# XMICRO-SERIAL_V1_1.net
KiCad netlist of a schematic drawn in EAGLE
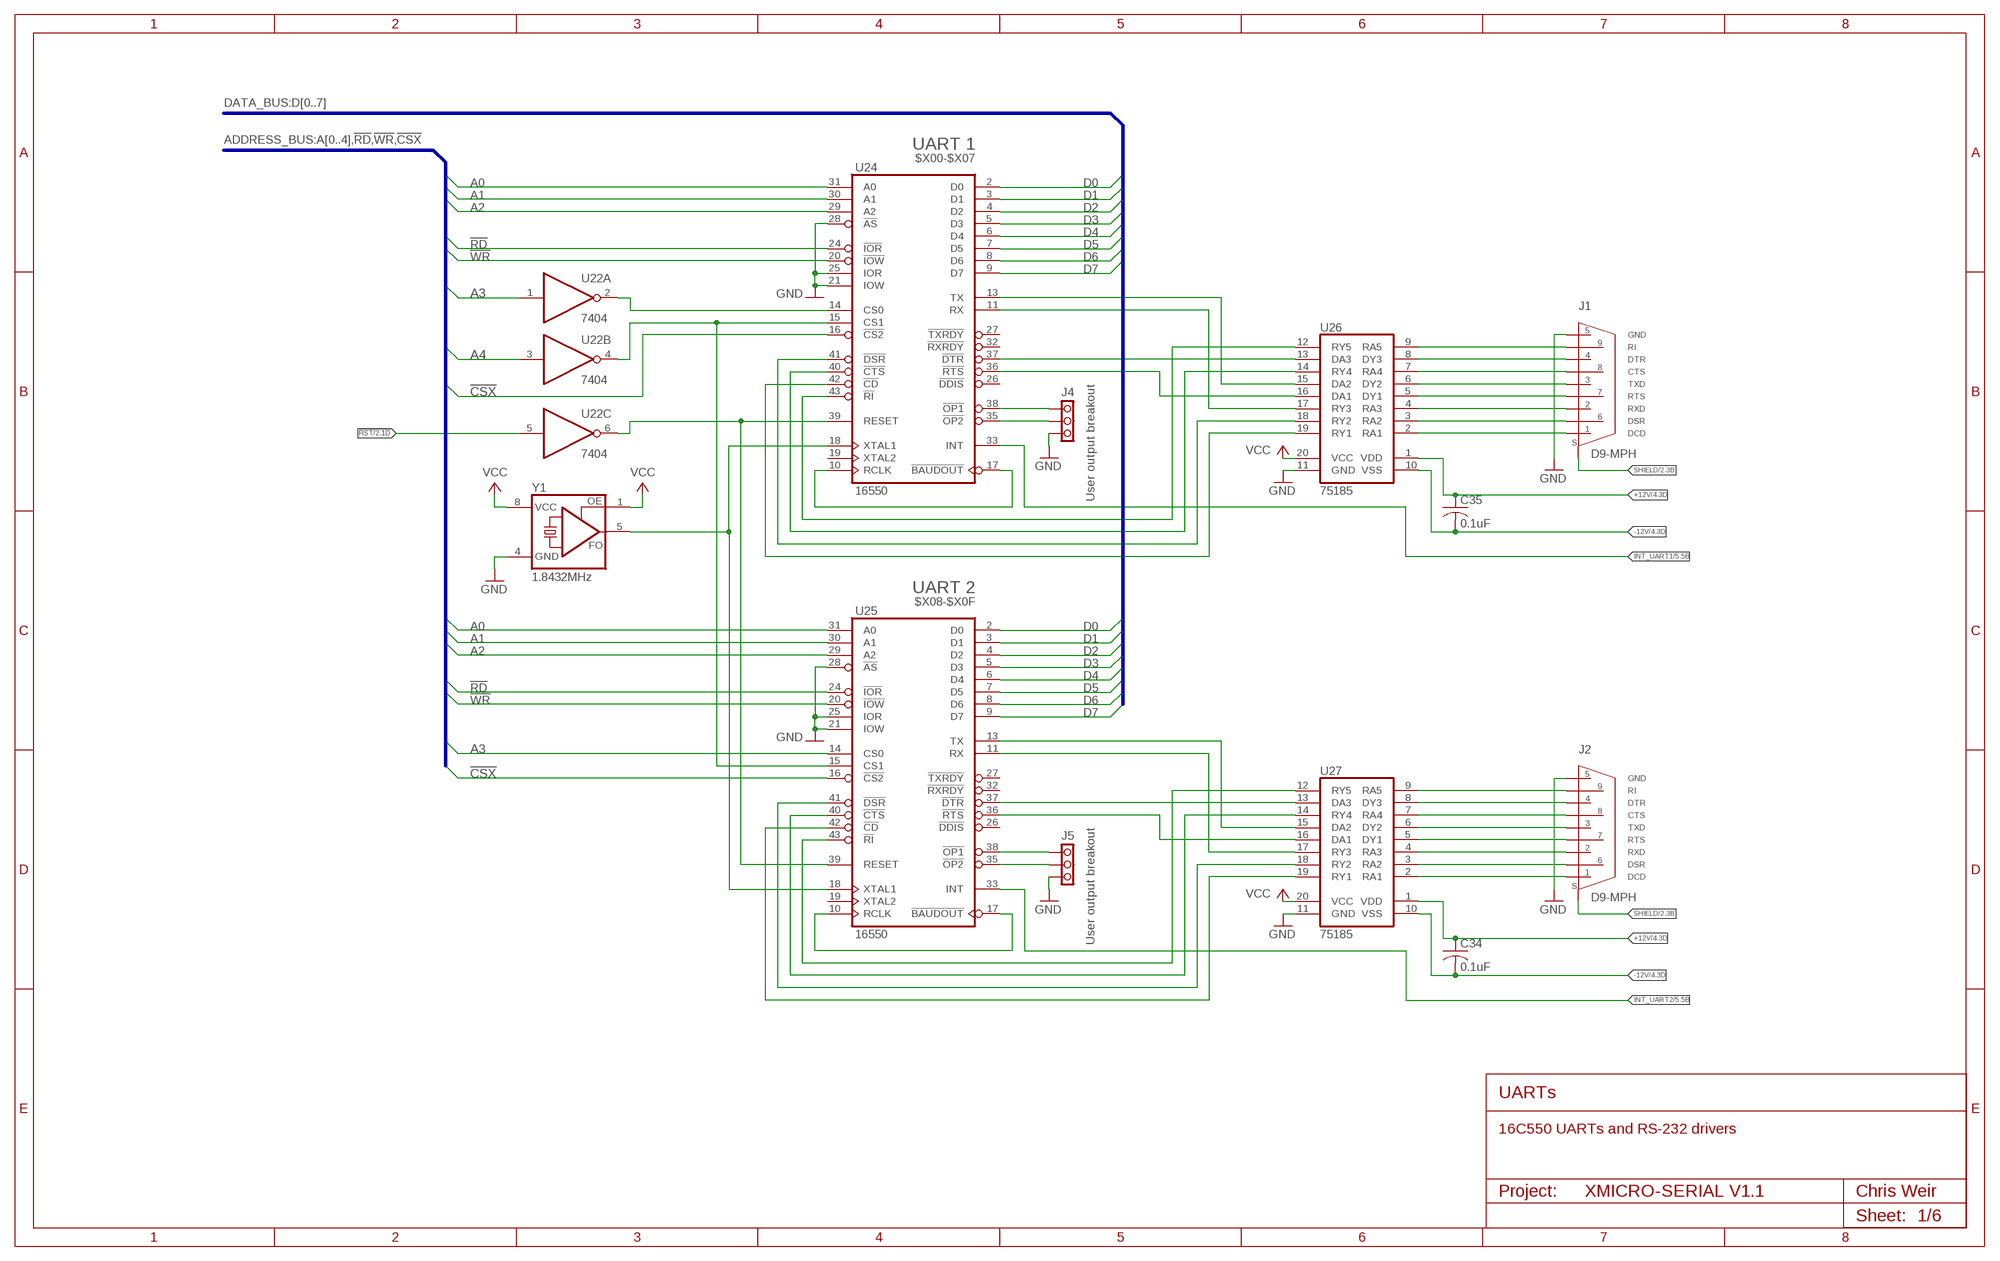
[diagram p0: schematic, sheet 1]
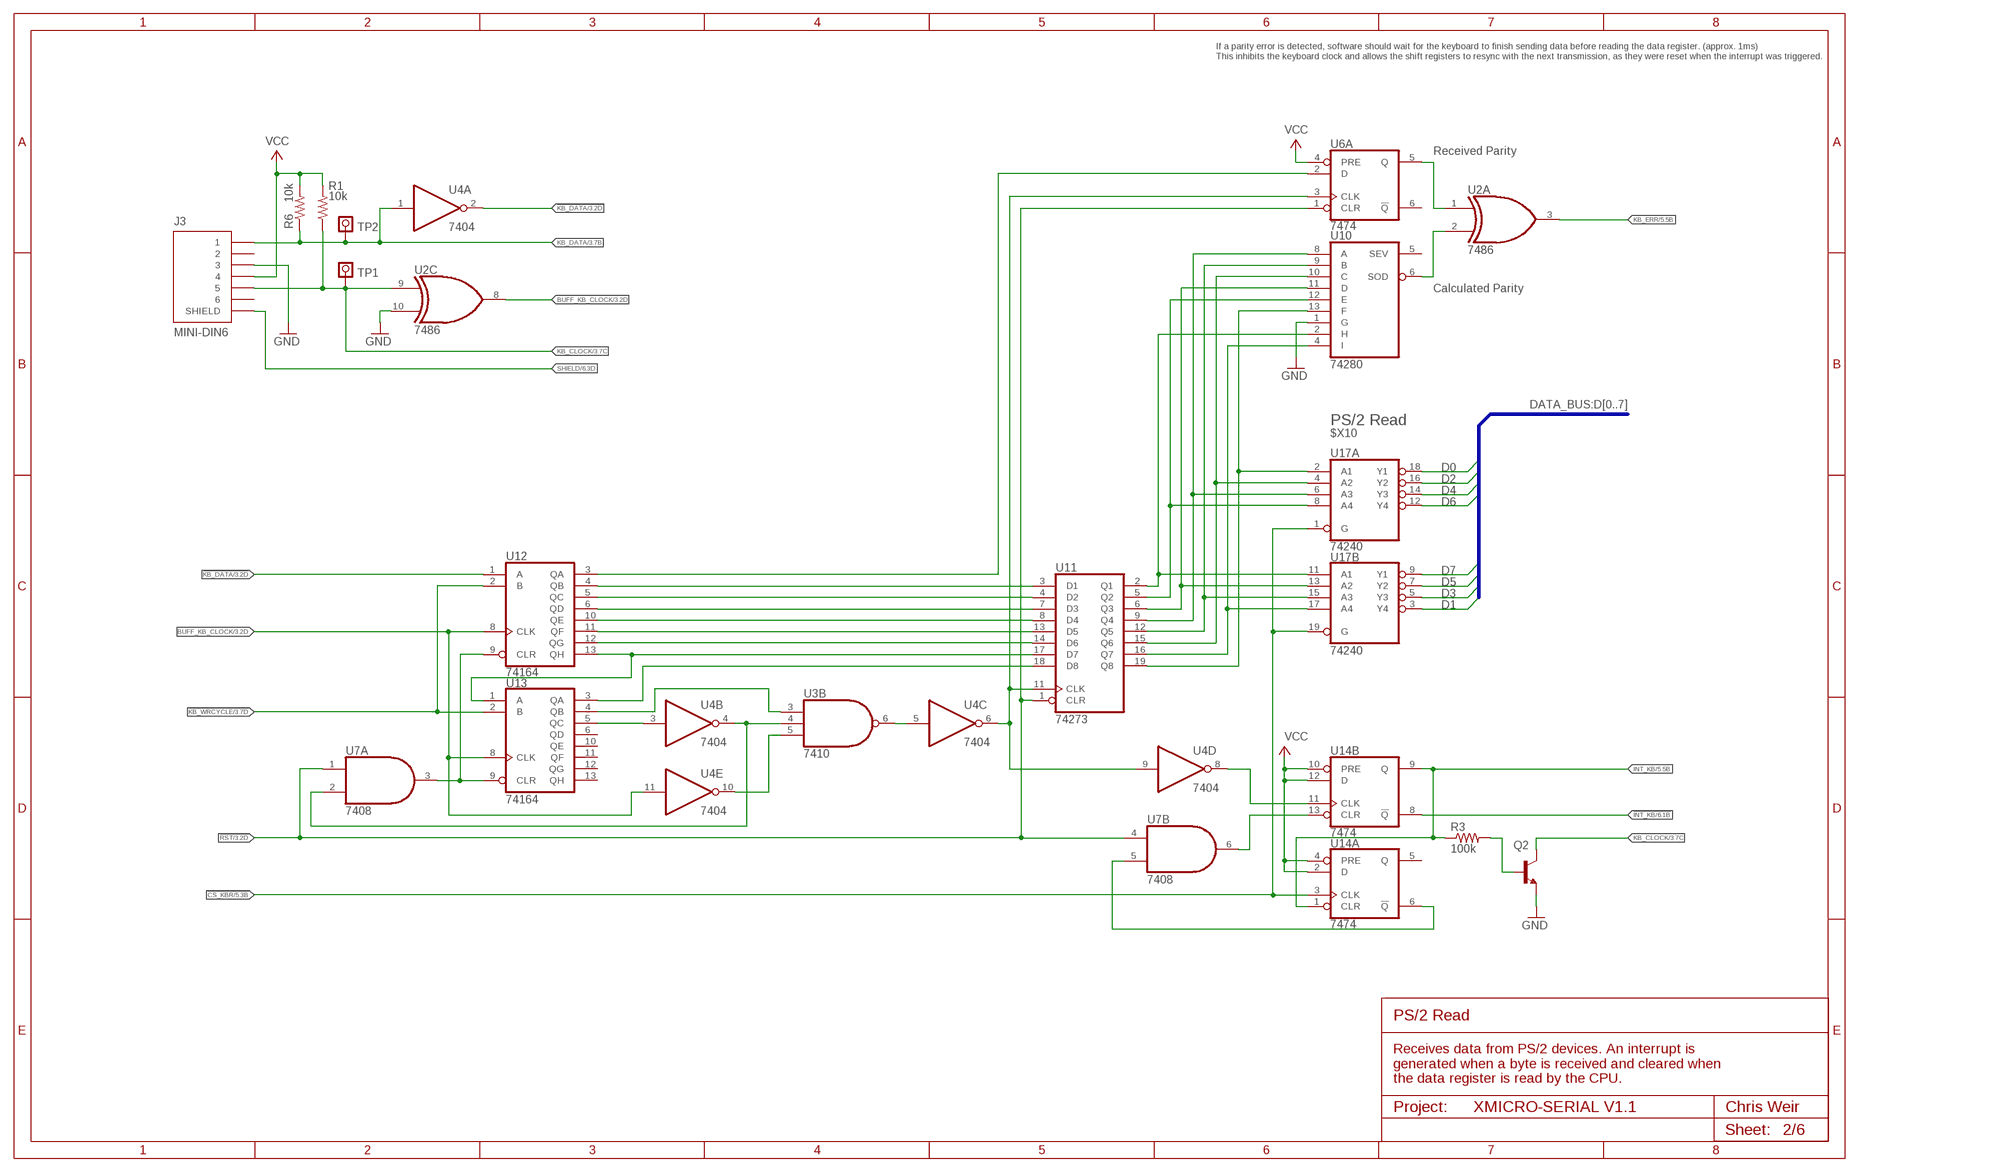
[diagram p1: schematic, sheet 2]
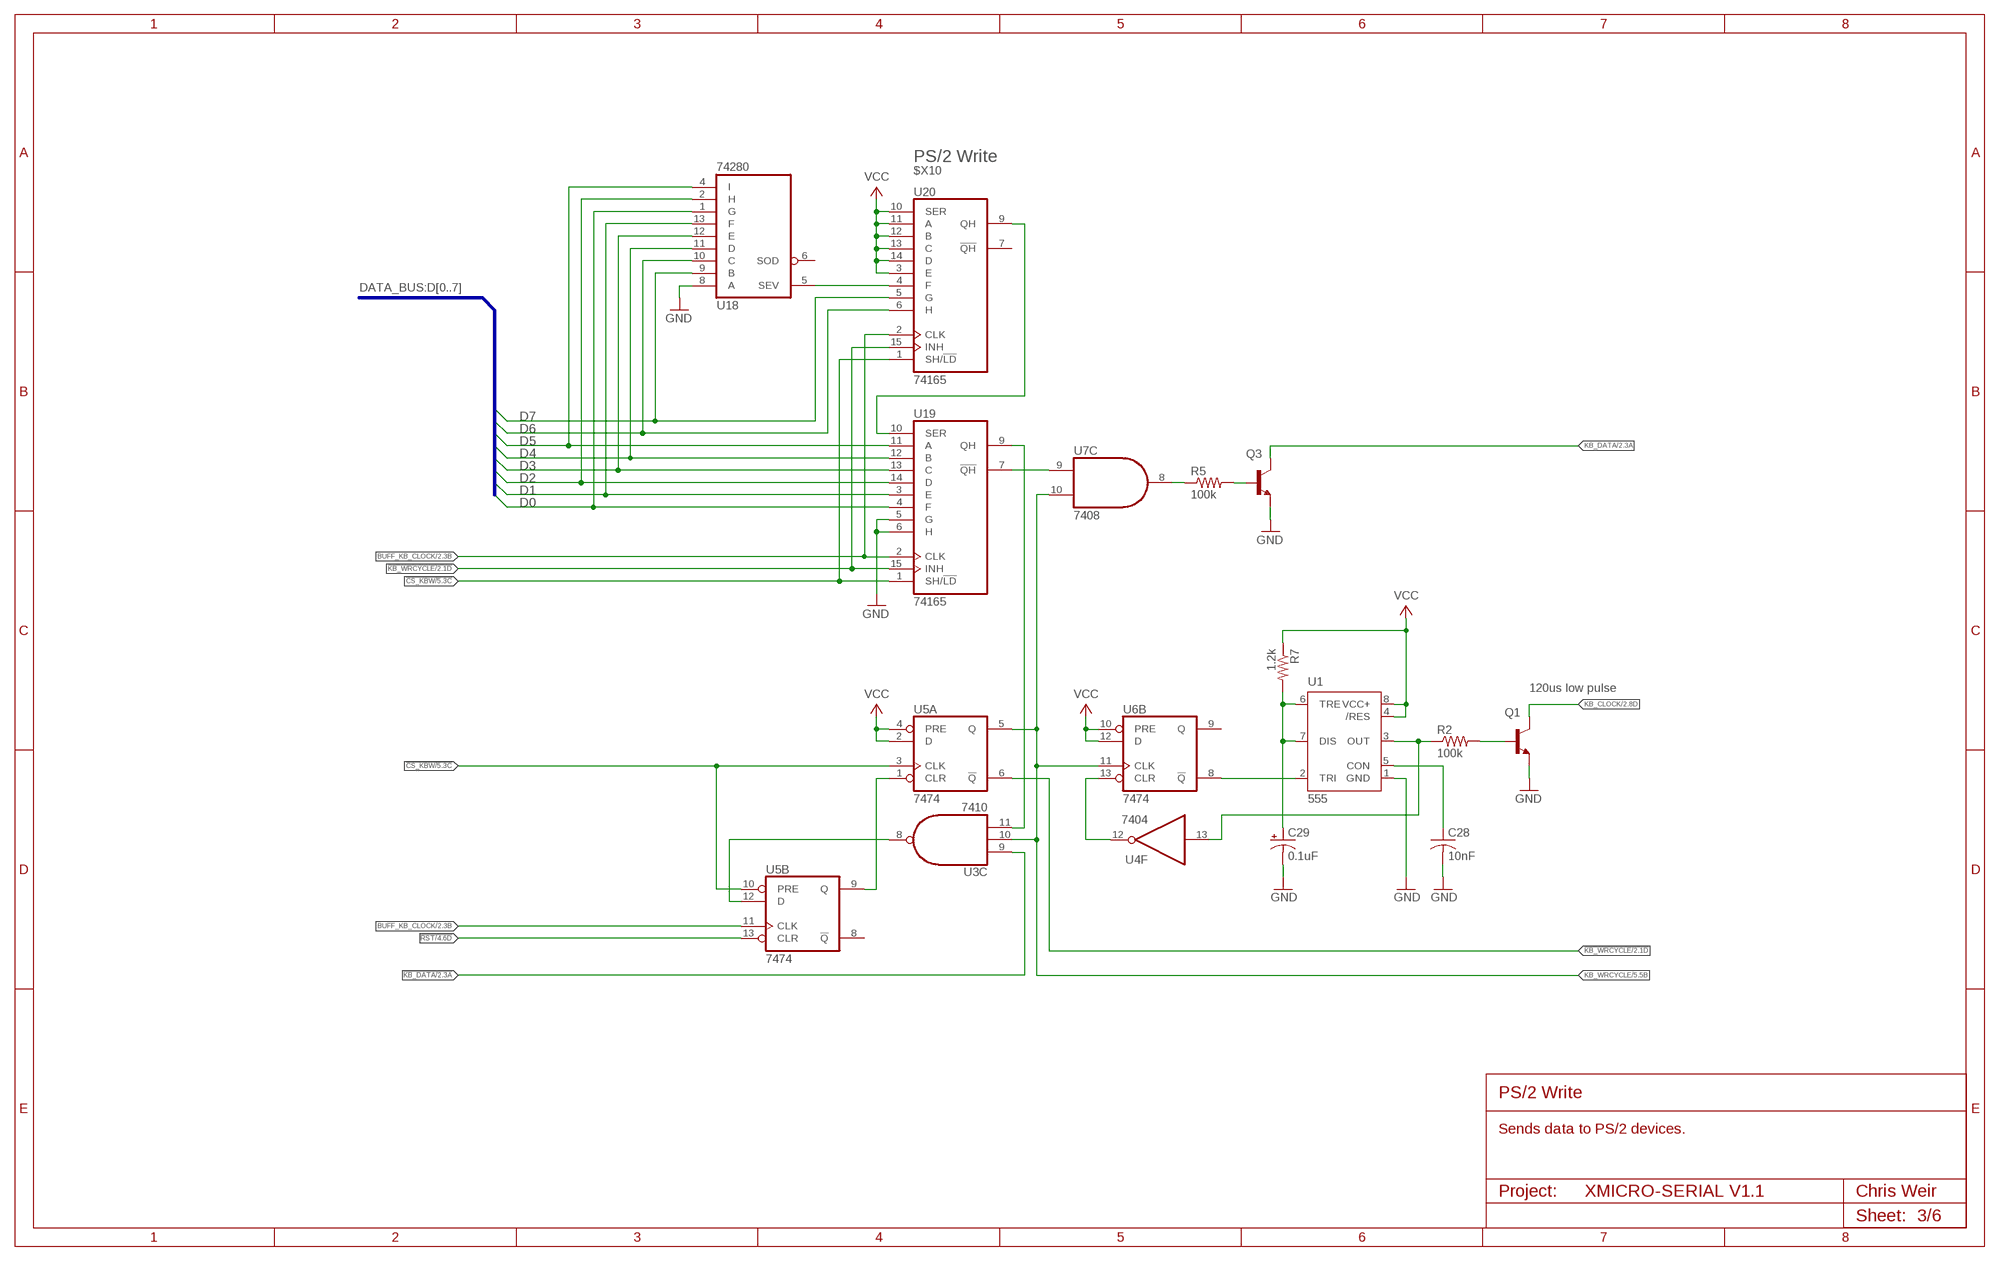
[diagram p2: schematic, sheet 3]
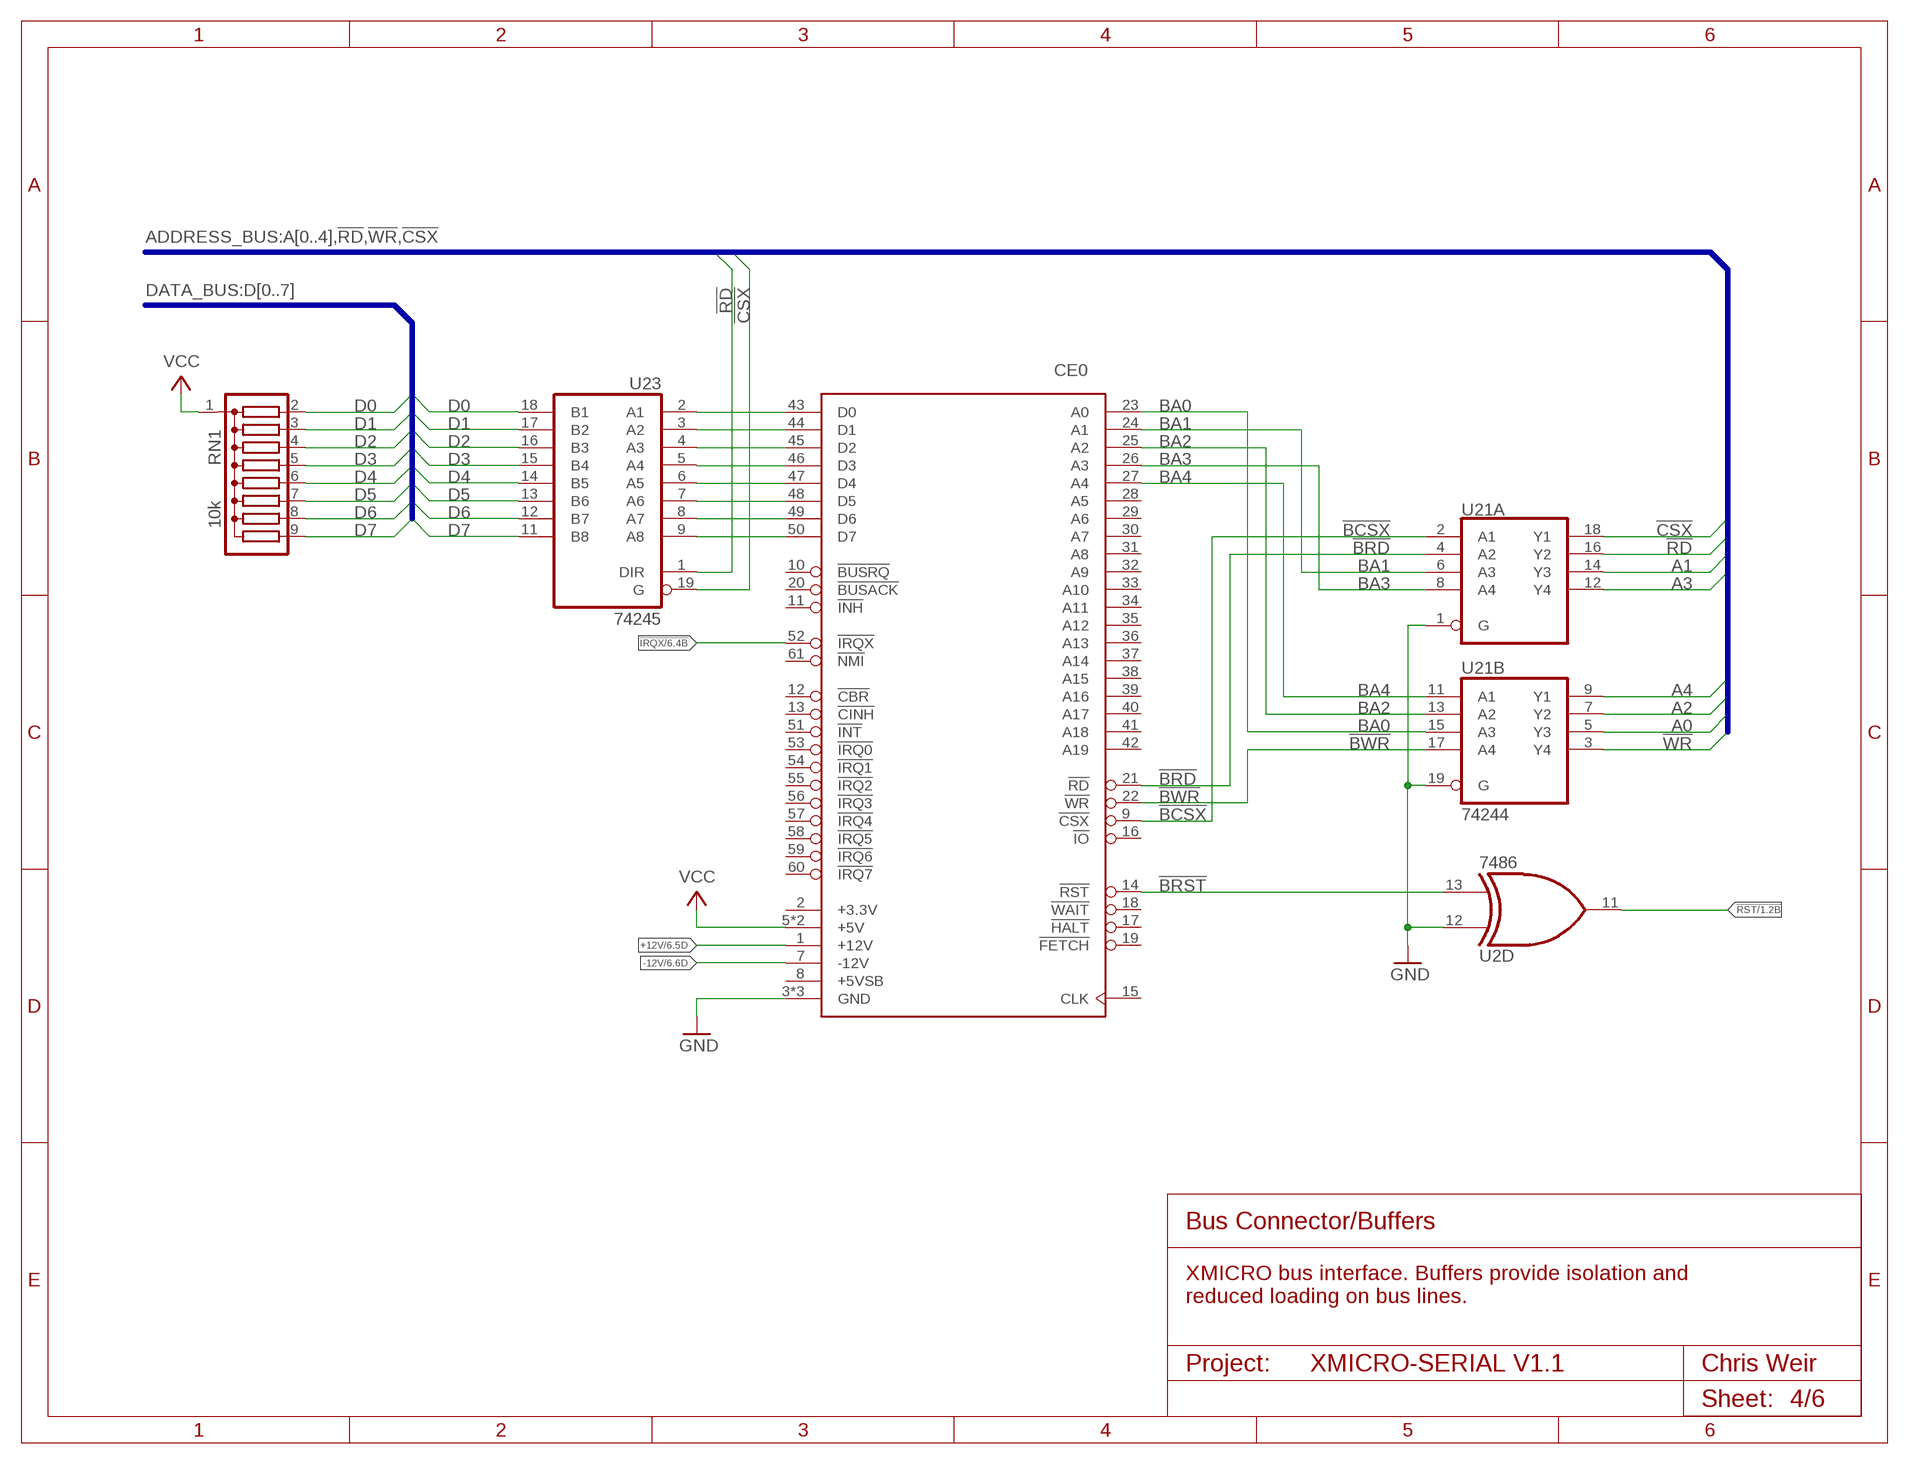
[diagram p3: schematic, sheet 4]
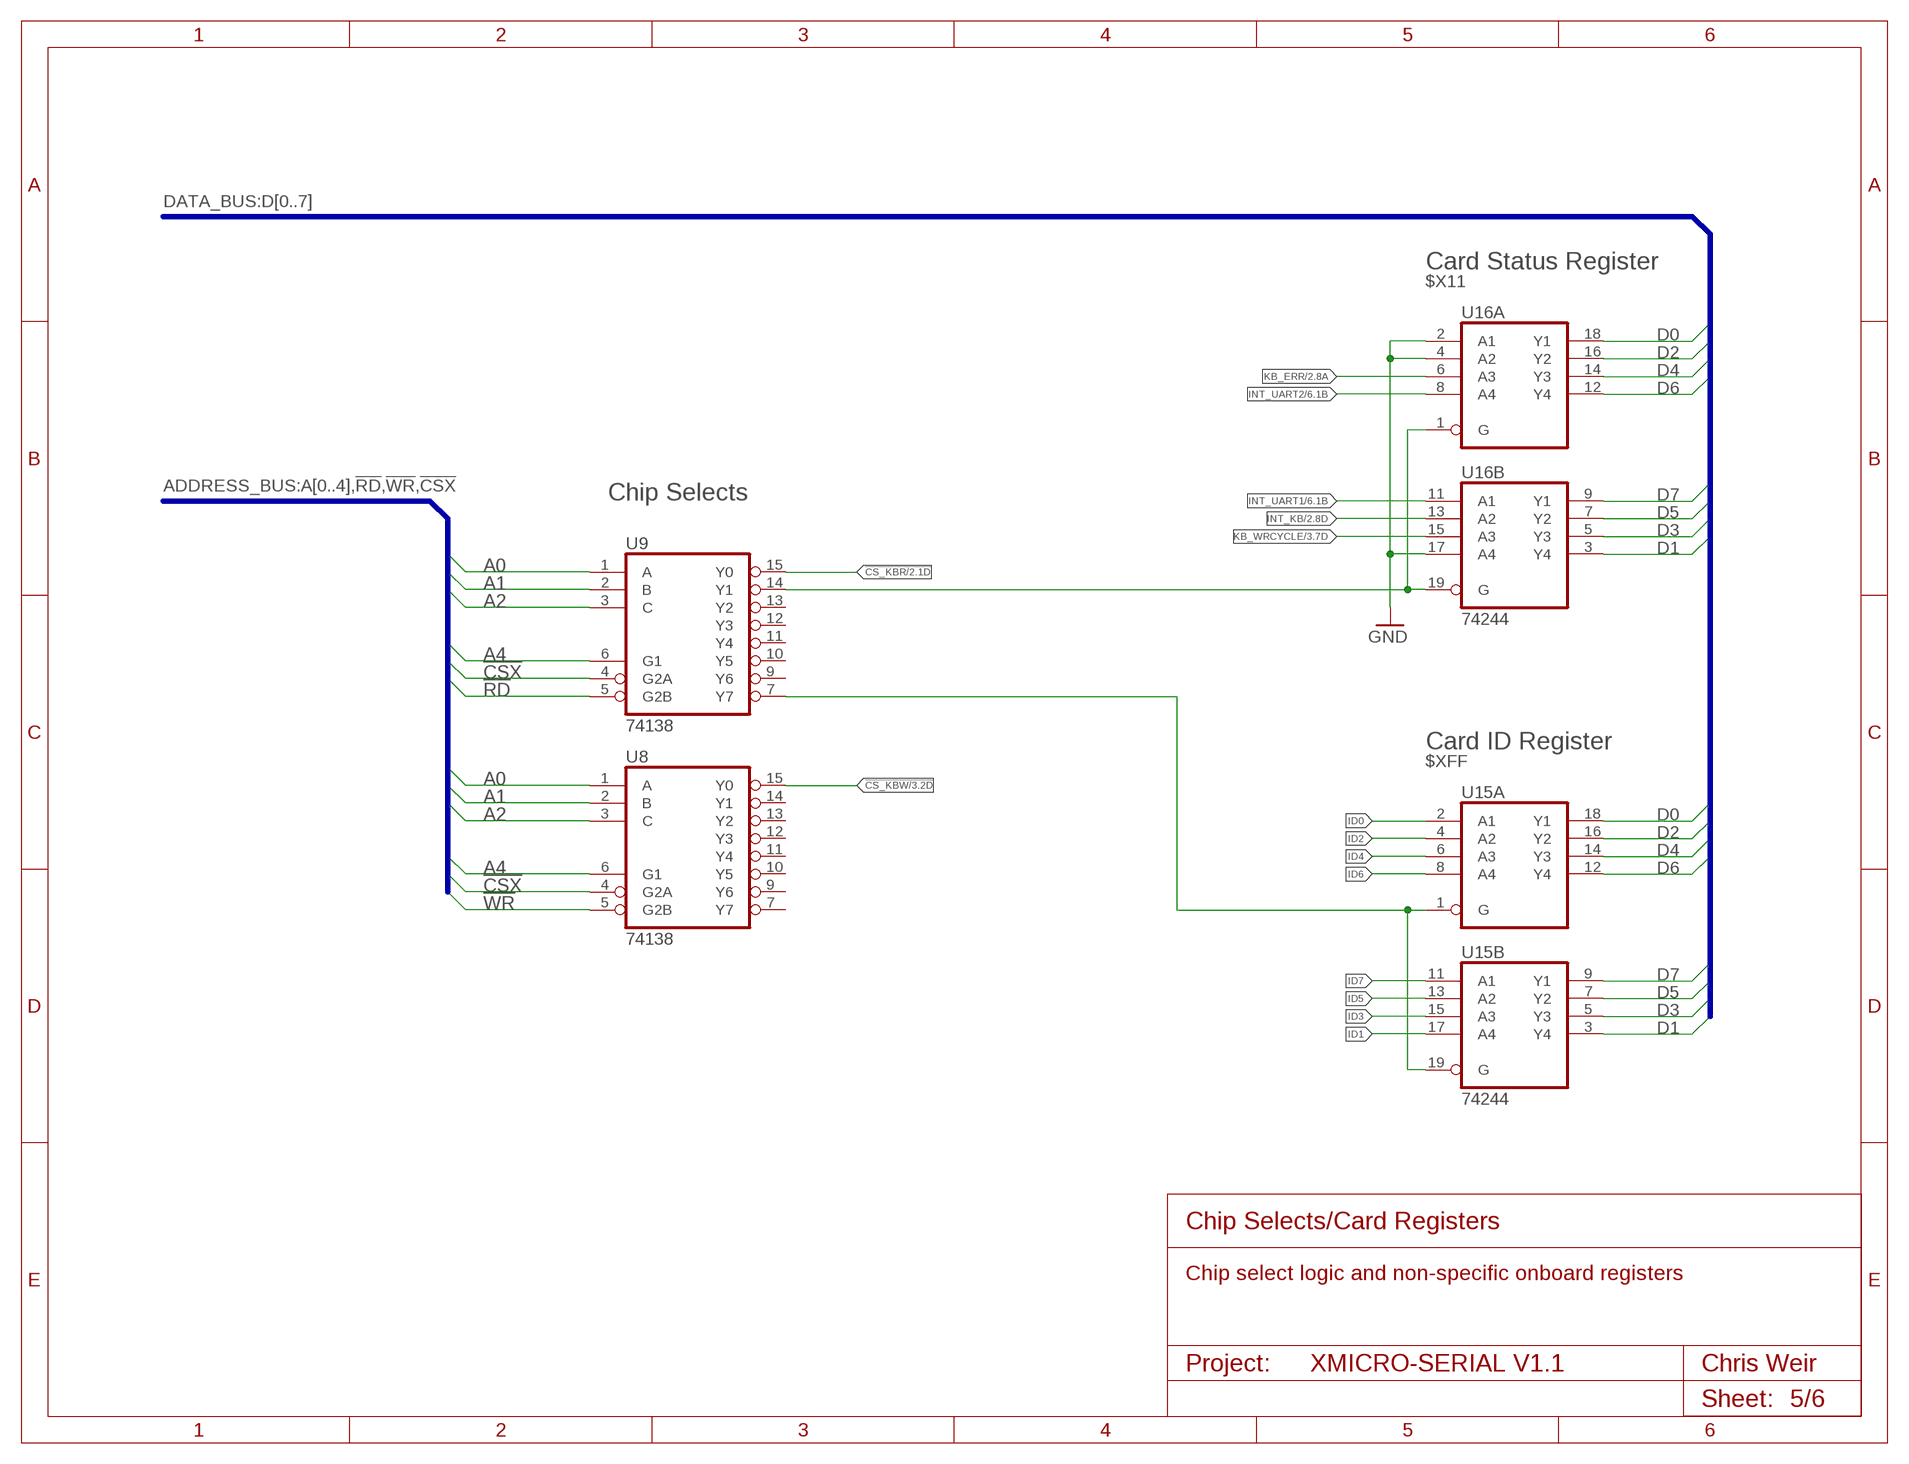
[diagram p4: schematic, sheet 5]
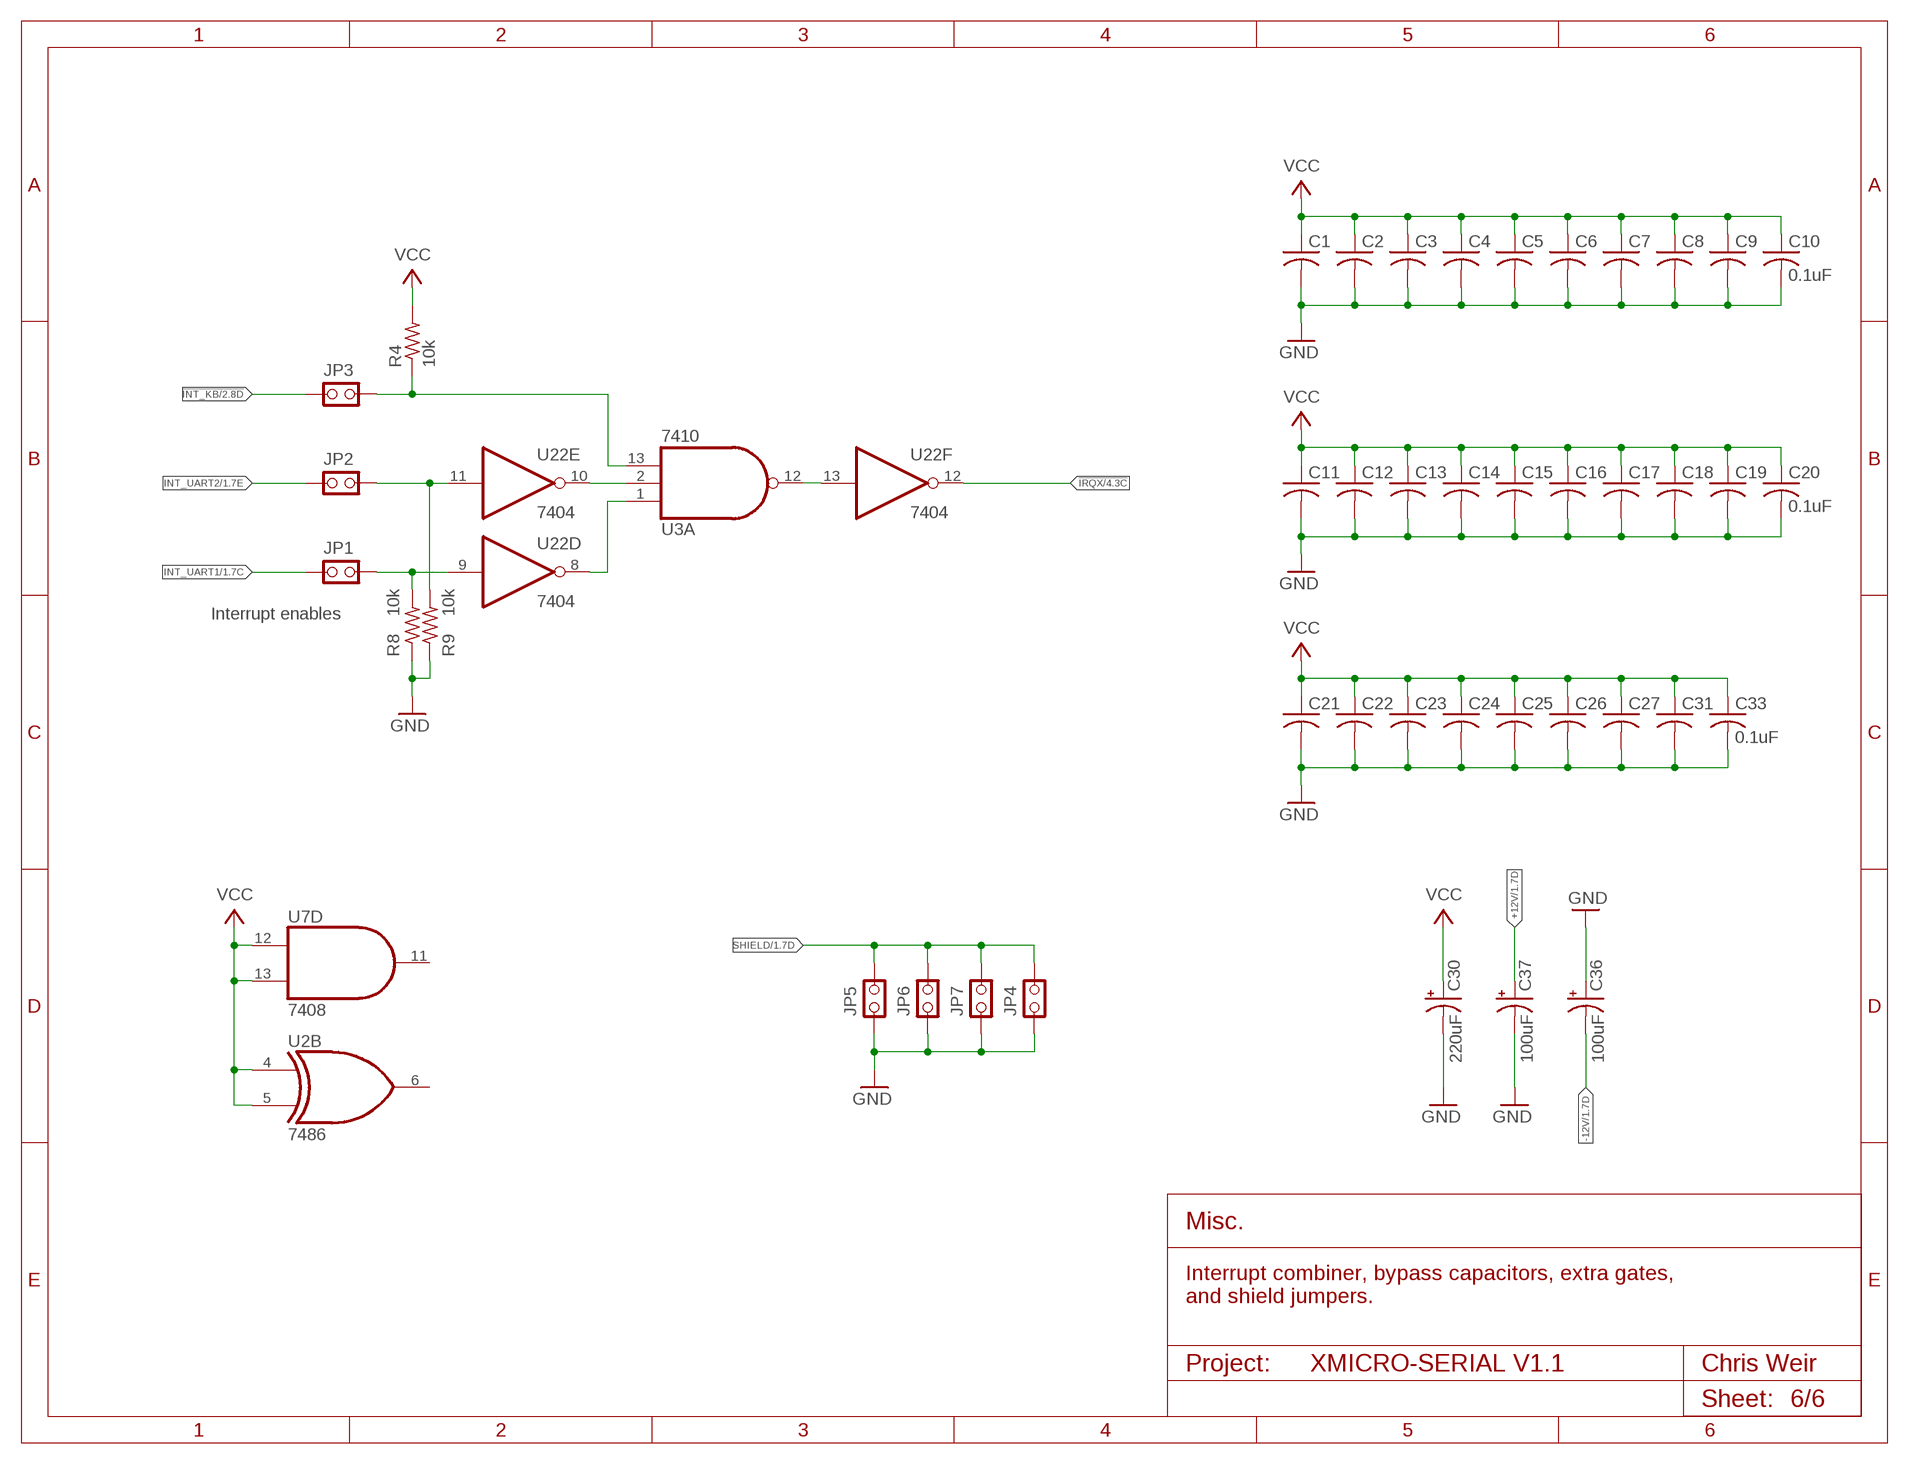
[diagram p5: schematic, sheet 6]

(export (version "E")
  (design (tool "Eeschema 10.0.6"))
  (components
    (comp (ref "C34")
      (value "0.1uF")
      (footprint "eagle-import:C100")
      (libsource (lib "eagle-import") (part "C-US100"))
    )
    (comp (ref "C35")
      (value "0.1uF")
      (footprint "eagle-import:C100")
      (libsource (lib "eagle-import") (part "C-US100"))
    )
    (comp (ref "J1")
      (value "D9-MPH")
      (footprint "eagle-import:D9-H")
      (libsource (lib "eagle-import") (part "D9-MPH"))
    )
    (comp (ref "J2")
      (value "D9-MPH")
      (footprint "eagle-import:D9-H")
      (libsource (lib "eagle-import") (part "D9-MPH"))
    )
    (comp (ref "J4")
      (value "PINHD1X3")
      (footprint "eagle-import:1X03")
      (libsource (lib "eagle-import") (part "PINHD1X3"))
    )
    (comp (ref "J5")
      (value "PINHD1X3")
      (footprint "eagle-import:1X03")
      (libsource (lib "eagle-import") (part "PINHD1X3"))
    )
    (comp (ref "U22")
      (value "7404")
      (footprint "eagle-import:DIL14")
      (libsource (lib "eagle-import") (part "7404NLS"))
    )
    (comp (ref "U24")
      (value "16550")
      (footprint "eagle-import:S44")
      (libsource (lib "eagle-import") (part "16C550S44"))
    )
    (comp (ref "U25")
      (value "16550")
      (footprint "eagle-import:S44")
      (libsource (lib "eagle-import") (part "16C550S44"))
    )
    (comp (ref "U26")
      (value "75185")
      (footprint "eagle-import:DIL20")
      (libsource (lib "eagle-import") (part "75C185N"))
    )
    (comp (ref "U27")
      (value "75185")
      (footprint "eagle-import:DIL20")
      (libsource (lib "eagle-import") (part "75C185N"))
    )
    (comp (ref "Y1")
      (value "1.8432MHz")
      (footprint "eagle-import:DIL08S")
      (libsource (lib "eagle-import") (part "OSC-OE"))
    )
    (comp (ref "C1")
      (value "0.1uF")
      (footprint "eagle-import:C100")
      (libsource (lib "eagle-import") (part "C-US100"))
    )
    (comp (ref "C2")
      (value "0.1uF")
      (footprint "eagle-import:C100")
      (libsource (lib "eagle-import") (part "C-US100"))
    )
    (comp (ref "C3")
      (value "0.1uF")
      (footprint "eagle-import:C100")
      (libsource (lib "eagle-import") (part "C-US100"))
    )
    (comp (ref "C4")
      (value "0.1uF")
      (footprint "eagle-import:C100")
      (libsource (lib "eagle-import") (part "C-US100"))
    )
    (comp (ref "C5")
      (value "0.1uF")
      (footprint "eagle-import:C100")
      (libsource (lib "eagle-import") (part "C-US100"))
    )
    (comp (ref "C6")
      (value "0.1uF")
      (footprint "eagle-import:C100")
      (libsource (lib "eagle-import") (part "C-US100"))
    )
    (comp (ref "C7")
      (value "0.1uF")
      (footprint "eagle-import:C100")
      (libsource (lib "eagle-import") (part "C-US100"))
    )
    (comp (ref "C8")
      (value "0.1uF")
      (footprint "eagle-import:C100")
      (libsource (lib "eagle-import") (part "C-US100"))
    )
    (comp (ref "C9")
      (value "0.1uF")
      (footprint "eagle-import:C100")
      (libsource (lib "eagle-import") (part "C-US100"))
    )
    (comp (ref "C10")
      (value "0.1uF")
      (footprint "eagle-import:C100")
      (libsource (lib "eagle-import") (part "C-US100"))
    )
    (comp (ref "C11")
      (value "0.1uF")
      (footprint "eagle-import:C100")
      (libsource (lib "eagle-import") (part "C-US100"))
    )
    (comp (ref "C12")
      (value "0.1uF")
      (footprint "eagle-import:C100")
      (libsource (lib "eagle-import") (part "C-US100"))
    )
    (comp (ref "C13")
      (value "0.1uF")
      (footprint "eagle-import:C100")
      (libsource (lib "eagle-import") (part "C-US100"))
    )
    (comp (ref "C14")
      (value "0.1uF")
      (footprint "eagle-import:C100")
      (libsource (lib "eagle-import") (part "C-US100"))
    )
    (comp (ref "C15")
      (value "0.1uF")
      (footprint "eagle-import:C100")
      (libsource (lib "eagle-import") (part "C-US100"))
    )
    (comp (ref "C16")
      (value "0.1uF")
      (footprint "eagle-import:C100")
      (libsource (lib "eagle-import") (part "C-US100"))
    )
    (comp (ref "C17")
      (value "0.1uF")
      (footprint "eagle-import:C100")
      (libsource (lib "eagle-import") (part "C-US100"))
    )
    (comp (ref "C18")
      (value "0.1uF")
      (footprint "eagle-import:C100")
      (libsource (lib "eagle-import") (part "C-US100"))
    )
    (comp (ref "C19")
      (value "0.1uF")
      (footprint "eagle-import:C100")
      (libsource (lib "eagle-import") (part "C-US100"))
    )
    (comp (ref "C20")
      (value "0.1uF")
      (footprint "eagle-import:C100")
      (libsource (lib "eagle-import") (part "C-US100"))
    )
    (comp (ref "C21")
      (value "0.1uF")
      (footprint "eagle-import:C100")
      (libsource (lib "eagle-import") (part "C-US100"))
    )
    (comp (ref "C22")
      (value "0.1uF")
      (footprint "eagle-import:C100")
      (libsource (lib "eagle-import") (part "C-US100"))
    )
    (comp (ref "C23")
      (value "0.1uF")
      (footprint "eagle-import:C100")
      (libsource (lib "eagle-import") (part "C-US100"))
    )
    (comp (ref "C24")
      (value "0.1uF")
      (footprint "eagle-import:C100")
      (libsource (lib "eagle-import") (part "C-US100"))
    )
    (comp (ref "C25")
      (value "0.1uF")
      (footprint "eagle-import:C100")
      (libsource (lib "eagle-import") (part "C-US100"))
    )
    (comp (ref "C26")
      (value "0.1uF")
      (footprint "eagle-import:C100")
      (libsource (lib "eagle-import") (part "C-US100"))
    )
    (comp (ref "C27")
      (value "0.1uF")
      (footprint "eagle-import:C100")
      (libsource (lib "eagle-import") (part "C-US100"))
    )
    (comp (ref "C30")
      (value "220uF")
      (footprint "eagle-import:C-10-5")
      (libsource (lib "eagle-import") (part "CPOL-US-10-5"))
    )
    (comp (ref "C31")
      (value "0.1uF")
      (footprint "eagle-import:C100")
      (libsource (lib "eagle-import") (part "C-US100"))
    )
    (comp (ref "C33")
      (value "0.1uF")
      (footprint "eagle-import:C100")
      (libsource (lib "eagle-import") (part "C-US100"))
    )
    (comp (ref "C36")
      (value "100uF")
      (footprint "eagle-import:E2,5-7")
      (libsource (lib "eagle-import") (part "CPOL-USE2.5-7"))
    )
    (comp (ref "C37")
      (value "100uF")
      (footprint "eagle-import:E2,5-7")
      (libsource (lib "eagle-import") (part "CPOL-USE2.5-7"))
    )
    (comp (ref "JP1")
      (value "PINHD-1X2THRU")
      (footprint "eagle-import:1X02")
      (libsource (lib "eagle-import") (part "PINHD-1X2THRU"))
    )
    (comp (ref "JP2")
      (value "PINHD-1X2THRU")
      (footprint "eagle-import:1X02")
      (libsource (lib "eagle-import") (part "PINHD-1X2THRU"))
    )
    (comp (ref "JP3")
      (value "PINHD-1X2THRU")
      (footprint "eagle-import:1X02")
      (libsource (lib "eagle-import") (part "PINHD-1X2THRU"))
    )
    (comp (ref "JP4")
      (value "PINHD-1X2THRU")
      (footprint "eagle-import:1X02")
      (libsource (lib "eagle-import") (part "PINHD-1X2THRU"))
    )
    (comp (ref "JP5")
      (value "PINHD-1X2THRU")
      (footprint "eagle-import:1X02")
      (libsource (lib "eagle-import") (part "PINHD-1X2THRU"))
    )
    (comp (ref "JP6")
      (value "PINHD-1X2THRU")
      (footprint "eagle-import:1X02")
      (libsource (lib "eagle-import") (part "PINHD-1X2THRU"))
    )
    (comp (ref "JP7")
      (value "PINHD-1X2THRU")
      (footprint "eagle-import:1X02")
      (libsource (lib "eagle-import") (part "PINHD-1X2THRU"))
    )
    (comp (ref "R4")
      (value "10k")
      (footprint "eagle-import:0207_10")
      (libsource (lib "eagle-import") (part "R-US_0207/10"))
    )
    (comp (ref "R8")
      (value "10k")
      (footprint "eagle-import:0207_10")
      (libsource (lib "eagle-import") (part "R-US_0207/10"))
    )
    (comp (ref "R9")
      (value "10k")
      (footprint "eagle-import:0207_10")
      (libsource (lib "eagle-import") (part "R-US_0207/10"))
    )
    (comp (ref "U2")
      (value "7486")
      (footprint "eagle-import:DIL14")
      (libsource (lib "eagle-import") (part "7486NLS"))
    )
    (comp (ref "U3")
      (value "7410")
      (footprint "eagle-import:DIL14")
      (libsource (lib "eagle-import") (part "7410NLS"))
    )
    (comp (ref "U7")
      (value "7408")
      (footprint "eagle-import:DIL14")
      (libsource (lib "eagle-import") (part "7408NLS"))
    )
    (comp (ref "C28")
      (value "10nF")
      (footprint "eagle-import:C100")
      (libsource (lib "eagle-import") (part "C-US100"))
    )
    (comp (ref "C29")
      (value "0.1uF")
      (footprint "eagle-import:E2,5-6")
      (libsource (lib "eagle-import") (part "CPOL-USE2.5-6"))
    )
    (comp (ref "Q1")
      (value "2N5088")
      (footprint "eagle-import:TO92")
      (libsource (lib "eagle-import") (part "TRANSISTOR-NPN-2N5088"))
    )
    (comp (ref "Q3")
      (value "2N5088")
      (footprint "eagle-import:TO92")
      (libsource (lib "eagle-import") (part "TRANSISTOR-NPN-2N5088"))
    )
    (comp (ref "R2")
      (value "100k")
      (footprint "eagle-import:0207_10")
      (libsource (lib "eagle-import") (part "R-US_0207/10"))
    )
    (comp (ref "R5")
      (value "100k")
      (footprint "eagle-import:0207_10")
      (libsource (lib "eagle-import") (part "R-US_0207/10"))
    )
    (comp (ref "R7")
      (value "1.2k")
      (footprint "eagle-import:0207_10")
      (libsource (lib "eagle-import") (part "R-US_0207/10"))
    )
    (comp (ref "U1")
      (value "555")
      (footprint "eagle-import:DIL-08")
      (fields (field (name "MF") "Arrow Electronics") (field (name "MPN") "NE555N"))
      (libsource (lib "eagle-import") (part "NE555"))
    )
    (comp (ref "U4")
      (value "7404")
      (footprint "eagle-import:DIL14")
      (libsource (lib "eagle-import") (part "74xx-us_7404NLS"))
    )
    (comp (ref "U5")
      (value "7474")
      (footprint "eagle-import:DIL14")
      (libsource (lib "eagle-import") (part "7474NLS"))
    )
    (comp (ref "U6")
      (value "7474")
      (footprint "eagle-import:DIL14")
      (libsource (lib "eagle-import") (part "7474NLS"))
    )
    (comp (ref "U18")
      (value "74280")
      (footprint "eagle-import:DIL14")
      (libsource (lib "eagle-import") (part "74280NLS"))
    )
    (comp (ref "U19")
      (value "74165")
      (footprint "eagle-import:DIL16")
      (libsource (lib "eagle-import") (part "74165NLS"))
    )
    (comp (ref "U20")
      (value "74165")
      (footprint "eagle-import:DIL16")
      (libsource (lib "eagle-import") (part "74165NLS"))
    )
    (comp (ref "CE0")
      (value "XMICRO-BUS-EDGE62M")
      (footprint "eagle-import:EDGE62M")
      (libsource (lib "eagle-import") (part "XMICRO-BUS-EDGE62M"))
    )
    (comp (ref "RN1")
      (value "10k")
      (footprint "eagle-import:SIL9")
      (fields (field (name "OC_FARNELL") "unknown") (field (name "OC_NEWARK") "unknown"))
      (libsource (lib "eagle-import") (part "G08R"))
    )
    (comp (ref "U21")
      (value "74244")
      (footprint "eagle-import:DIL20")
      (libsource (lib "eagle-import") (part "74244NLS"))
    )
    (comp (ref "U23")
      (value "74245")
      (footprint "eagle-import:DIL20")
      (libsource (lib "eagle-import") (part "74245NLS"))
    )
    (comp (ref "U8")
      (value "74138")
      (footprint "eagle-import:DIL16")
      (libsource (lib "eagle-import") (part "74138NLS"))
    )
    (comp (ref "U9")
      (value "74138")
      (footprint "eagle-import:DIL16")
      (libsource (lib "eagle-import") (part "74138NLS"))
    )
    (comp (ref "U15")
      (value "74244")
      (footprint "eagle-import:DIL20")
      (libsource (lib "eagle-import") (part "74244NLS"))
    )
    (comp (ref "U16")
      (value "74244")
      (footprint "eagle-import:DIL20")
      (libsource (lib "eagle-import") (part "74244NLS"))
    )
    (comp (ref "J3")
      (value "MINI-DIN6")
      (footprint "eagle-import:MINI-DIN6")
      (libsource (lib "eagle-import") (part "MINI-DIN6"))
    )
    (comp (ref "Q2")
      (value "2N5088")
      (footprint "eagle-import:TO92")
      (libsource (lib "eagle-import") (part "TRANSISTOR-NPN-2N5088"))
    )
    (comp (ref "R1")
      (value "10k")
      (footprint "eagle-import:0207_10")
      (libsource (lib "eagle-import") (part "R-US_0207/10"))
    )
    (comp (ref "R3")
      (value "100k")
      (footprint "eagle-import:0207_10")
      (libsource (lib "eagle-import") (part "R-US_0207/10"))
    )
    (comp (ref "R6")
      (value "10k")
      (footprint "eagle-import:0207_10")
      (libsource (lib "eagle-import") (part "R-US_0207/10"))
    )
    (comp (ref "TP1")
      (value "PINHD-1X1")
      (footprint "eagle-import:1X01")
      (libsource (lib "eagle-import") (part "PINHD-1X1"))
    )
    (comp (ref "TP2")
      (value "PINHD-1X1")
      (footprint "eagle-import:1X01")
      (libsource (lib "eagle-import") (part "PINHD-1X1"))
    )
    (comp (ref "U10")
      (value "74280")
      (footprint "eagle-import:DIL14")
      (libsource (lib "eagle-import") (part "74280NLS"))
    )
    (comp (ref "U11")
      (value "74273")
      (footprint "eagle-import:DIL20")
      (libsource (lib "eagle-import") (part "74273N"))
    )
    (comp (ref "U12")
      (value "74164")
      (footprint "eagle-import:DIL14")
      (libsource (lib "eagle-import") (part "74164NHCT"))
    )
    (comp (ref "U13")
      (value "74164")
      (footprint "eagle-import:DIL14")
      (libsource (lib "eagle-import") (part "74164NHCT"))
    )
    (comp (ref "U14")
      (value "7474")
      (footprint "eagle-import:DIL14")
      (libsource (lib "eagle-import") (part "7474NLS"))
    )
    (comp (ref "U17")
      (value "74240")
      (footprint "eagle-import:DIL20")
      (libsource (lib "eagle-import") (part "74240NLS"))
    )
  )
  (nets
    (net (code "41") (name "+12V") (class "Default")
      (node (ref "C34") (pin "P$1") (pinfunction "1_P$1") (pintype "passive"))
      (node (ref "C35") (pin "P$1") (pinfunction "1_P$1") (pintype "passive"))
      (node (ref "C37") (pin "+") (pinfunction "+_+") (pintype "passive"))
      (node (ref "CE0") (pin "1") (pinfunction "+12V_1") (pintype "bidirectional"))
      (node (ref "U26") (pin "1") (pinfunction "VDD_1") (pintype "power_in"))
      (node (ref "U27") (pin "1") (pinfunction "VDD_1") (pintype "power_in"))
    )
    (net (code "42") (name "-12V") (class "Default")
      (node (ref "C34") (pin "P$2") (pinfunction "2_P$2") (pintype "passive"))
      (node (ref "C35") (pin "P$2") (pinfunction "2_P$2") (pintype "passive"))
      (node (ref "C36") (pin "-") (pinfunction "-_-") (pintype "passive"))
      (node (ref "CE0") (pin "7") (pinfunction "-12V_7") (pintype "bidirectional"))
      (node (ref "U26") (pin "10") (pinfunction "VSS_10") (pintype "power_in"))
      (node (ref "U27") (pin "10") (pinfunction "VSS_10") (pintype "power_in"))
    )
    (net (code "51") (name "A0") (class "Default")
      (node (ref "U21") (pin "5") (pinfunction "Y3_5") (pintype "tri_state"))
      (node (ref "U24") (pin "31") (pinfunction "A0_31") (pintype "input"))
      (node (ref "U25") (pin "31") (pinfunction "A0_31") (pintype "input"))
      (node (ref "U8") (pin "1") (pinfunction "A_1") (pintype "input"))
      (node (ref "U9") (pin "1") (pinfunction "A_1") (pintype "input"))
    )
    (net (code "52") (name "A1") (class "Default")
      (node (ref "U21") (pin "14") (pinfunction "Y3_14") (pintype "tri_state"))
      (node (ref "U24") (pin "30") (pinfunction "A1_30") (pintype "input"))
      (node (ref "U25") (pin "30") (pinfunction "A1_30") (pintype "input"))
      (node (ref "U8") (pin "2") (pinfunction "B_2") (pintype "input"))
      (node (ref "U9") (pin "2") (pinfunction "B_2") (pintype "input"))
    )
    (net (code "53") (name "A2") (class "Default")
      (node (ref "U21") (pin "7") (pinfunction "Y2_7") (pintype "tri_state"))
      (node (ref "U24") (pin "29") (pinfunction "A2_29") (pintype "input"))
      (node (ref "U25") (pin "29") (pinfunction "A2_29") (pintype "input"))
      (node (ref "U8") (pin "3") (pinfunction "C_3") (pintype "input"))
      (node (ref "U9") (pin "3") (pinfunction "C_3") (pintype "input"))
    )
    (net (code "54") (name "A3") (class "Default")
      (node (ref "U21") (pin "12") (pinfunction "Y4_12") (pintype "tri_state"))
      (node (ref "U22") (pin "1") (pinfunction "I_1") (pintype "input"))
      (node (ref "U25") (pin "14") (pinfunction "CS0_14") (pintype "input"))
    )
    (net (code "55") (name "A4") (class "Default")
      (node (ref "U21") (pin "9") (pinfunction "Y1_9") (pintype "tri_state"))
      (node (ref "U22") (pin "3") (pinfunction "I_3") (pintype "input"))
      (node (ref "U8") (pin "6") (pinfunction "G1_6") (pintype "input"))
      (node (ref "U9") (pin "6") (pinfunction "G1_6") (pintype "input"))
    )
    (net (code "56") (name "BA0") (class "Default")
      (node (ref "CE0") (pin "23") (pinfunction "A0_23") (pintype "bidirectional"))
      (node (ref "U21") (pin "15") (pinfunction "A3_15") (pintype "input"))
    )
    (net (code "57") (name "BA1") (class "Default")
      (node (ref "CE0") (pin "24") (pinfunction "A1_24") (pintype "bidirectional"))
      (node (ref "U21") (pin "6") (pinfunction "A3_6") (pintype "input"))
    )
    (net (code "58") (name "BA2") (class "Default")
      (node (ref "CE0") (pin "25") (pinfunction "A2_25") (pintype "bidirectional"))
      (node (ref "U21") (pin "13") (pinfunction "A2_13") (pintype "input"))
    )
    (net (code "59") (name "BA3") (class "Default")
      (node (ref "CE0") (pin "26") (pinfunction "A3_26") (pintype "bidirectional"))
      (node (ref "U21") (pin "8") (pinfunction "A4_8") (pintype "input"))
    )
    (net (code "60") (name "BA4") (class "Default")
      (node (ref "CE0") (pin "27") (pinfunction "A4_27") (pintype "bidirectional"))
      (node (ref "U21") (pin "11") (pinfunction "A1_11") (pintype "input"))
    )
    (net (code "61") (name "BUFF_KB_CLOCK") (class "Default")
      (node (ref "U12") (pin "8") (pinfunction "CLK_8") (pintype "input"))
      (node (ref "U13") (pin "8") (pinfunction "CLK_8") (pintype "input"))
      (node (ref "U19") (pin "2") (pinfunction "CLK_2") (pintype "input"))
      (node (ref "U2") (pin "8") (pinfunction "O_8") (pintype "output"))
      (node (ref "U20") (pin "2") (pinfunction "CLK_2") (pintype "input"))
      (node (ref "U4") (pin "11") (pinfunction "I_11") (pintype "input"))
      (node (ref "U5") (pin "11") (pinfunction "CLK_11") (pintype "input"))
    )
    (net (code "62") (name "D0") (class "Default")
      (node (ref "RN1") (pin "2") (pinfunction "2_2") (pintype "passive"))
      (node (ref "U15") (pin "18") (pinfunction "Y1_18") (pintype "tri_state"))
      (node (ref "U16") (pin "18") (pinfunction "Y1_18") (pintype "tri_state"))
      (node (ref "U17") (pin "18") (pinfunction "Y1_18") (pintype "tri_state"))
      (node (ref "U18") (pin "1") (pinfunction "G_1") (pintype "input"))
      (node (ref "U19") (pin "4") (pinfunction "F_4") (pintype "input"))
      (node (ref "U23") (pin "18") (pinfunction "B1_18") (pintype "bidirectional"))
      (node (ref "U24") (pin "2") (pinfunction "D0_2") (pintype "tri_state"))
      (node (ref "U25") (pin "2") (pinfunction "D0_2") (pintype "tri_state"))
    )
    (net (code "63") (name "D1") (class "Default")
      (node (ref "RN1") (pin "3") (pinfunction "3_3") (pintype "passive"))
      (node (ref "U15") (pin "3") (pinfunction "Y4_3") (pintype "tri_state"))
      (node (ref "U16") (pin "3") (pinfunction "Y4_3") (pintype "tri_state"))
      (node (ref "U17") (pin "3") (pinfunction "Y4_3") (pintype "tri_state"))
      (node (ref "U18") (pin "13") (pinfunction "F_13") (pintype "input"))
      (node (ref "U19") (pin "3") (pinfunction "E_3") (pintype "input"))
      (node (ref "U23") (pin "17") (pinfunction "B2_17") (pintype "bidirectional"))
      (node (ref "U24") (pin "3") (pinfunction "D1_3") (pintype "tri_state"))
      (node (ref "U25") (pin "3") (pinfunction "D1_3") (pintype "tri_state"))
    )
    (net (code "64") (name "D2") (class "Default")
      (node (ref "RN1") (pin "4") (pinfunction "4_4") (pintype "passive"))
      (node (ref "U15") (pin "16") (pinfunction "Y2_16") (pintype "tri_state"))
      (node (ref "U16") (pin "16") (pinfunction "Y2_16") (pintype "tri_state"))
      (node (ref "U17") (pin "16") (pinfunction "Y2_16") (pintype "tri_state"))
      (node (ref "U18") (pin "2") (pinfunction "H_2") (pintype "input"))
      (node (ref "U19") (pin "14") (pinfunction "D_14") (pintype "input"))
      (node (ref "U23") (pin "16") (pinfunction "B3_16") (pintype "bidirectional"))
      (node (ref "U24") (pin "4") (pinfunction "D2_4") (pintype "tri_state"))
      (node (ref "U25") (pin "4") (pinfunction "D2_4") (pintype "tri_state"))
    )
    (net (code "65") (name "D3") (class "Default")
      (node (ref "RN1") (pin "5") (pinfunction "5_5") (pintype "passive"))
      (node (ref "U15") (pin "5") (pinfunction "Y3_5") (pintype "tri_state"))
      (node (ref "U16") (pin "5") (pinfunction "Y3_5") (pintype "tri_state"))
      (node (ref "U17") (pin "5") (pinfunction "Y3_5") (pintype "tri_state"))
      (node (ref "U18") (pin "12") (pinfunction "E_12") (pintype "input"))
      (node (ref "U19") (pin "13") (pinfunction "C_13") (pintype "input"))
      (node (ref "U23") (pin "15") (pinfunction "B4_15") (pintype "bidirectional"))
      (node (ref "U24") (pin "5") (pinfunction "D3_5") (pintype "tri_state"))
      (node (ref "U25") (pin "5") (pinfunction "D3_5") (pintype "tri_state"))
    )
    (net (code "66") (name "D4") (class "Default")
      (node (ref "RN1") (pin "6") (pinfunction "6_6") (pintype "passive"))
      (node (ref "U15") (pin "14") (pinfunction "Y3_14") (pintype "tri_state"))
      (node (ref "U16") (pin "14") (pinfunction "Y3_14") (pintype "tri_state"))
      (node (ref "U17") (pin "14") (pinfunction "Y3_14") (pintype "tri_state"))
      (node (ref "U18") (pin "11") (pinfunction "D_11") (pintype "input"))
      (node (ref "U19") (pin "12") (pinfunction "B_12") (pintype "input"))
      (node (ref "U23") (pin "14") (pinfunction "B5_14") (pintype "bidirectional"))
      (node (ref "U24") (pin "6") (pinfunction "D4_6") (pintype "tri_state"))
      (node (ref "U25") (pin "6") (pinfunction "D4_6") (pintype "tri_state"))
    )
    (net (code "67") (name "D5") (class "Default")
      (node (ref "RN1") (pin "7") (pinfunction "7_7") (pintype "passive"))
      (node (ref "U15") (pin "7") (pinfunction "Y2_7") (pintype "tri_state"))
      (node (ref "U16") (pin "7") (pinfunction "Y2_7") (pintype "tri_state"))
      (node (ref "U17") (pin "7") (pinfunction "Y2_7") (pintype "tri_state"))
      (node (ref "U18") (pin "4") (pinfunction "I_4") (pintype "input"))
      (node (ref "U19") (pin "11") (pinfunction "A_11") (pintype "input"))
      (node (ref "U23") (pin "13") (pinfunction "B6_13") (pintype "bidirectional"))
      (node (ref "U24") (pin "7") (pinfunction "D5_7") (pintype "tri_state"))
      (node (ref "U25") (pin "7") (pinfunction "D5_7") (pintype "tri_state"))
    )
    (net (code "68") (name "D6") (class "Default")
      (node (ref "RN1") (pin "8") (pinfunction "8_8") (pintype "passive"))
      (node (ref "U15") (pin "12") (pinfunction "Y4_12") (pintype "tri_state"))
      (node (ref "U16") (pin "12") (pinfunction "Y4_12") (pintype "tri_state"))
      (node (ref "U17") (pin "12") (pinfunction "Y4_12") (pintype "tri_state"))
      (node (ref "U18") (pin "10") (pinfunction "C_10") (pintype "input"))
      (node (ref "U20") (pin "6") (pinfunction "H_6") (pintype "input"))
      (node (ref "U23") (pin "12") (pinfunction "B7_12") (pintype "bidirectional"))
      (node (ref "U24") (pin "8") (pinfunction "D6_8") (pintype "tri_state"))
      (node (ref "U25") (pin "8") (pinfunction "D6_8") (pintype "tri_state"))
    )
    (net (code "69") (name "D7") (class "Default")
      (node (ref "RN1") (pin "9") (pinfunction "9_9") (pintype "passive"))
      (node (ref "U15") (pin "9") (pinfunction "Y1_9") (pintype "tri_state"))
      (node (ref "U16") (pin "9") (pinfunction "Y1_9") (pintype "tri_state"))
      (node (ref "U17") (pin "9") (pinfunction "Y1_9") (pintype "tri_state"))
      (node (ref "U18") (pin "9") (pinfunction "B_9") (pintype "input"))
      (node (ref "U20") (pin "5") (pinfunction "G_5") (pintype "input"))
      (node (ref "U23") (pin "11") (pinfunction "B8_11") (pintype "bidirectional"))
      (node (ref "U24") (pin "9") (pinfunction "D7_9") (pintype "tri_state"))
      (node (ref "U25") (pin "9") (pinfunction "D7_9") (pintype "tri_state"))
    )
    (net (code "70") (name "GND") (class "Default")
      (node (ref "C1") (pin "P$2") (pinfunction "2_P$2") (pintype "passive"))
      (node (ref "C10") (pin "P$2") (pinfunction "2_P$2") (pintype "passive"))
      (node (ref "C11") (pin "P$2") (pinfunction "2_P$2") (pintype "passive"))
      (node (ref "C12") (pin "P$2") (pinfunction "2_P$2") (pintype "passive"))
      (node (ref "C13") (pin "P$2") (pinfunction "2_P$2") (pintype "passive"))
      (node (ref "C14") (pin "P$2") (pinfunction "2_P$2") (pintype "passive"))
      (node (ref "C15") (pin "P$2") (pinfunction "2_P$2") (pintype "passive"))
      (node (ref "C16") (pin "P$2") (pinfunction "2_P$2") (pintype "passive"))
      (node (ref "C17") (pin "P$2") (pinfunction "2_P$2") (pintype "passive"))
      (node (ref "C18") (pin "P$2") (pinfunction "2_P$2") (pintype "passive"))
      (node (ref "C19") (pin "P$2") (pinfunction "2_P$2") (pintype "passive"))
      (node (ref "C2") (pin "P$2") (pinfunction "2_P$2") (pintype "passive"))
      (node (ref "C20") (pin "P$2") (pinfunction "2_P$2") (pintype "passive"))
      (node (ref "C21") (pin "P$2") (pinfunction "2_P$2") (pintype "passive"))
      (node (ref "C22") (pin "P$2") (pinfunction "2_P$2") (pintype "passive"))
      (node (ref "C23") (pin "P$2") (pinfunction "2_P$2") (pintype "passive"))
      (node (ref "C24") (pin "P$2") (pinfunction "2_P$2") (pintype "passive"))
      (node (ref "C25") (pin "P$2") (pinfunction "2_P$2") (pintype "passive"))
      (node (ref "C26") (pin "P$2") (pinfunction "2_P$2") (pintype "passive"))
      (node (ref "C27") (pin "P$2") (pinfunction "2_P$2") (pintype "passive"))
      (node (ref "C28") (pin "P$2") (pinfunction "2_P$2") (pintype "passive"))
      (node (ref "C29") (pin "-") (pinfunction "-_-") (pintype "passive"))
      (node (ref "C3") (pin "P$2") (pinfunction "2_P$2") (pintype "passive"))
      (node (ref "C30") (pin "-") (pinfunction "-_-") (pintype "passive"))
      (node (ref "C31") (pin "P$2") (pinfunction "2_P$2") (pintype "passive"))
      (node (ref "C33") (pin "P$2") (pinfunction "2_P$2") (pintype "passive"))
      (node (ref "C36") (pin "+") (pinfunction "+_+") (pintype "passive"))
      (node (ref "C37") (pin "-") (pinfunction "-_-") (pintype "passive"))
      (node (ref "C4") (pin "P$2") (pinfunction "2_P$2") (pintype "passive"))
      (node (ref "C5") (pin "P$2") (pinfunction "2_P$2") (pintype "passive"))
      (node (ref "C6") (pin "P$2") (pinfunction "2_P$2") (pintype "passive"))
      (node (ref "C7") (pin "P$2") (pinfunction "2_P$2") (pintype "passive"))
      (node (ref "C8") (pin "P$2") (pinfunction "2_P$2") (pintype "passive"))
      (node (ref "C9") (pin "P$2") (pinfunction "2_P$2") (pintype "passive"))
      (node (ref "CE0") (pin "3") (pinfunction "GND_3") (pintype "bidirectional"))
      (node (ref "CE0") (pin "4") (pinfunction "GND_4") (pintype "bidirectional"))
      (node (ref "CE0") (pin "62") (pinfunction "GND_62") (pintype "bidirectional"))
      (node (ref "J1") (pin "P$5") (pinfunction "P$5_P$5") (pintype "bidirectional"))
      (node (ref "J2") (pin "P$5") (pinfunction "P$5_P$5") (pintype "bidirectional"))
      (node (ref "J3") (pin "3") (pinfunction "3_3") (pintype "bidirectional"))
      (node (ref "J4") (pin "3") (pinfunction "3_3") (pintype "passive"))
      (node (ref "J5") (pin "3") (pinfunction "3_3") (pintype "passive"))
      (node (ref "JP4") (pin "1") (pinfunction "1_1") (pintype "passive"))
      (node (ref "JP5") (pin "1") (pinfunction "1_1") (pintype "passive"))
      (node (ref "JP6") (pin "1") (pinfunction "1_1") (pintype "passive"))
      (node (ref "JP7") (pin "1") (pinfunction "1_1") (pintype "passive"))
      (node (ref "Q1") (pin "1") (pinfunction "E_1") (pintype "passive"))
      (node (ref "Q2") (pin "1") (pinfunction "E_1") (pintype "passive"))
      (node (ref "Q3") (pin "1") (pinfunction "E_1") (pintype "passive"))
      (node (ref "R8") (pin "1") (pinfunction "1_1") (pintype "passive"))
      (node (ref "R9") (pin "1") (pinfunction "1_1") (pintype "passive"))
      (node (ref "U1") (pin "1") (pinfunction "GND_1") (pintype "power_in"))
      (node (ref "U10") (pin "1") (pinfunction "G_1") (pintype "input"))
      (node (ref "U16") (pin "17") (pinfunction "A4_17") (pintype "input"))
      (node (ref "U16") (pin "2") (pinfunction "A1_2") (pintype "input"))
      (node (ref "U16") (pin "4") (pinfunction "A2_4") (pintype "input"))
      (node (ref "U18") (pin "8") (pinfunction "A_8") (pintype "input"))
      (node (ref "U19") (pin "5") (pinfunction "G_5") (pintype "input"))
      (node (ref "U19") (pin "6") (pinfunction "H_6") (pintype "input"))
      (node (ref "U2") (pin "10") (pinfunction "I1_10") (pintype "input"))
      (node (ref "U2") (pin "12") (pinfunction "I0_12") (pintype "input"))
      (node (ref "U21") (pin "1") (pinfunction "G_1") (pintype "input"))
      (node (ref "U21") (pin "19") (pinfunction "G_19") (pintype "input"))
      (node (ref "U24") (pin "21") (pinfunction "IOW_21") (pintype "input"))
      (node (ref "U24") (pin "25") (pinfunction "IOR_25") (pintype "input"))
      (node (ref "U24") (pin "28") (pinfunction "~{AS}_28") (pintype "input"))
      (node (ref "U25") (pin "21") (pinfunction "IOW_21") (pintype "input"))
      (node (ref "U25") (pin "25") (pinfunction "IOR_25") (pintype "input"))
      (node (ref "U25") (pin "28") (pinfunction "~{AS}_28") (pintype "input"))
      (node (ref "U26") (pin "11") (pinfunction "GND_11") (pintype "power_in"))
      (node (ref "U27") (pin "11") (pinfunction "GND_11") (pintype "power_in"))
      (node (ref "Y1") (pin "4") (pinfunction "GND_4") (pintype "power_in"))
    )
    (net (code "71") (name "ID0") (class "Default")
      (node (ref "U15") (pin "2") (pinfunction "A1_2") (pintype "input"))
    )
    (net (code "72") (name "ID1") (class "Default")
      (node (ref "U15") (pin "17") (pinfunction "A4_17") (pintype "input"))
    )
    (net (code "73") (name "ID2") (class "Default")
      (node (ref "U15") (pin "4") (pinfunction "A2_4") (pintype "input"))
    )
    (net (code "74") (name "ID3") (class "Default")
      (node (ref "U15") (pin "15") (pinfunction "A3_15") (pintype "input"))
    )
    (net (code "75") (name "ID4") (class "Default")
      (node (ref "U15") (pin "6") (pinfunction "A3_6") (pintype "input"))
    )
    (net (code "76") (name "ID5") (class "Default")
      (node (ref "U15") (pin "13") (pinfunction "A2_13") (pintype "input"))
    )
    (net (code "77") (name "ID6") (class "Default")
      (node (ref "U15") (pin "8") (pinfunction "A4_8") (pintype "input"))
    )
    (net (code "78") (name "ID7") (class "Default")
      (node (ref "U15") (pin "11") (pinfunction "A1_11") (pintype "input"))
    )
    (net (code "79") (name "INT_KB") (class "Default")
      (node (ref "R3") (pin "1") (pinfunction "1_1") (pintype "passive"))
      (node (ref "U14") (pin "1") (pinfunction "CLR_1") (pintype "input"))
      (node (ref "U14") (pin "9") (pinfunction "Q_9") (pintype "output"))
      (node (ref "U16") (pin "13") (pinfunction "A2_13") (pintype "input"))
    )
    (net (code "80") (name "INT_UART1") (class "Default")
      (node (ref "JP1") (pin "1") (pinfunction "1_1") (pintype "passive"))
      (node (ref "U16") (pin "11") (pinfunction "A1_11") (pintype "input"))
      (node (ref "U24") (pin "33") (pinfunction "INT_33") (pintype "output"))
    )
    (net (code "81") (name "INT_UART2") (class "Default")
      (node (ref "JP2") (pin "1") (pinfunction "1_1") (pintype "passive"))
      (node (ref "U16") (pin "8") (pinfunction "A4_8") (pintype "input"))
      (node (ref "U25") (pin "33") (pinfunction "INT_33") (pintype "output"))
    )
    (net (code "82") (name "KB_CLOCK") (class "Default")
      (node (ref "J3") (pin "5") (pinfunction "5_5") (pintype "bidirectional"))
      (node (ref "Q1") (pin "3") (pinfunction "C_3") (pintype "passive"))
      (node (ref "Q2") (pin "3") (pinfunction "C_3") (pintype "passive"))
      (node (ref "R1") (pin "1") (pinfunction "1_1") (pintype "passive"))
      (node (ref "TP1") (pin "1") (pinfunction "1_1") (pintype "passive"))
      (node (ref "U2") (pin "9") (pinfunction "I0_9") (pintype "input"))
    )
    (net (code "83") (name "KB_DATA") (class "Default")
      (node (ref "J3") (pin "1") (pinfunction "1_1") (pintype "bidirectional"))
      (node (ref "Q3") (pin "3") (pinfunction "C_3") (pintype "passive"))
      (node (ref "R6") (pin "1") (pinfunction "1_1") (pintype "passive"))
      (node (ref "TP2") (pin "1") (pinfunction "1_1") (pintype "passive"))
      (node (ref "U4") (pin "1") (pinfunction "I_1") (pintype "input"))
    )
    (net (code "84") (name "KB_ERR") (class "Default")
      (node (ref "U16") (pin "6") (pinfunction "A3_6") (pintype "input"))
      (node (ref "U2") (pin "3") (pinfunction "O_3") (pintype "output"))
    )
    (net (code "85") (name "KB_WRCYCLE") (class "Default")
      (node (ref "U16") (pin "15") (pinfunction "A3_15") (pintype "input"))
      (node (ref "U3") (pin "10") (pinfunction "I1_10") (pintype "input"))
      (node (ref "U5") (pin "5") (pinfunction "Q_5") (pintype "output"))
      (node (ref "U6") (pin "11") (pinfunction "CLK_11") (pintype "input"))
      (node (ref "U7") (pin "10") (pinfunction "I1_10") (pintype "input"))
    )
    (net (code "86") (name "Net-(C28-1)") (class "Default")
      (node (ref "C28") (pin "P$1") (pinfunction "1_P$1") (pintype "passive"))
      (node (ref "U1") (pin "5") (pinfunction "CON_5") (pintype "input"))
    )
    (net (code "87") (name "Net-(CE0-D0)") (class "Default")
      (node (ref "CE0") (pin "43") (pinfunction "D0_43") (pintype "bidirectional"))
      (node (ref "U23") (pin "2") (pinfunction "A1_2") (pintype "bidirectional"))
    )
    (net (code "88") (name "Net-(CE0-D1)") (class "Default")
      (node (ref "CE0") (pin "44") (pinfunction "D1_44") (pintype "bidirectional"))
      (node (ref "U23") (pin "3") (pinfunction "A2_3") (pintype "bidirectional"))
    )
    (net (code "89") (name "Net-(CE0-D2)") (class "Default")
      (node (ref "CE0") (pin "45") (pinfunction "D2_45") (pintype "bidirectional"))
      (node (ref "U23") (pin "4") (pinfunction "A3_4") (pintype "bidirectional"))
    )
    (net (code "90") (name "Net-(CE0-D3)") (class "Default")
      (node (ref "CE0") (pin "46") (pinfunction "D3_46") (pintype "bidirectional"))
      (node (ref "U23") (pin "5") (pinfunction "A4_5") (pintype "bidirectional"))
    )
    (net (code "91") (name "Net-(CE0-D4)") (class "Default")
      (node (ref "CE0") (pin "47") (pinfunction "D4_47") (pintype "bidirectional"))
      (node (ref "U23") (pin "6") (pinfunction "A5_6") (pintype "bidirectional"))
    )
    (net (code "92") (name "Net-(CE0-D5)") (class "Default")
      (node (ref "CE0") (pin "48") (pinfunction "D5_48") (pintype "bidirectional"))
      (node (ref "U23") (pin "7") (pinfunction "A6_7") (pintype "bidirectional"))
    )
    (net (code "93") (name "Net-(CE0-D6)") (class "Default")
      (node (ref "CE0") (pin "49") (pinfunction "D6_49") (pintype "bidirectional"))
      (node (ref "U23") (pin "8") (pinfunction "A7_8") (pintype "bidirectional"))
    )
    (net (code "94") (name "Net-(CE0-D7)") (class "Default")
      (node (ref "CE0") (pin "50") (pinfunction "D7_50") (pintype "bidirectional"))
      (node (ref "U23") (pin "9") (pinfunction "A8_9") (pintype "bidirectional"))
    )
    (net (code "95") (name "Net-(Q1-B)") (class "Default")
      (node (ref "Q1") (pin "2") (pinfunction "B_2") (pintype "passive"))
      (node (ref "R2") (pin "2") (pinfunction "2_2") (pintype "passive"))
    )
    (net (code "96") (name "Net-(Q2-B)") (class "Default")
      (node (ref "Q2") (pin "2") (pinfunction "B_2") (pintype "passive"))
      (node (ref "R3") (pin "2") (pinfunction "2_2") (pintype "passive"))
    )
    (net (code "97") (name "Net-(Q3-B)") (class "Default")
      (node (ref "Q3") (pin "2") (pinfunction "B_2") (pintype "passive"))
      (node (ref "R5") (pin "2") (pinfunction "2_2") (pintype "passive"))
    )
    (net (code "98") (name "Net-(U1-DIS)") (class "Default")
      (node (ref "C29") (pin "+") (pinfunction "+_+") (pintype "passive"))
      (node (ref "R7") (pin "2") (pinfunction "2_2") (pintype "passive"))
      (node (ref "U1") (pin "6") (pinfunction "TRE_6") (pintype "input"))
      (node (ref "U1") (pin "7") (pinfunction "DIS_7") (pintype "input"))
    )
    (net (code "99") (name "Net-(U1-OUT)") (class "Default")
      (node (ref "R2") (pin "1") (pinfunction "1_1") (pintype "passive"))
      (node (ref "U1") (pin "3") (pinfunction "OUT_3") (pintype "output"))
      (node (ref "U4") (pin "13") (pinfunction "I_13") (pintype "input"))
    )
    (net (code "100") (name "Net-(U1-TRI)") (class "Default")
      (node (ref "U1") (pin "2") (pinfunction "TRI_2") (pintype "input"))
      (node (ref "U6") (pin "8") (pinfunction "~{Q}_8") (pintype "output"))
    )
    (net (code "101") (name "Net-(U2A-I0)") (class "Default")
      (node (ref "U2") (pin "1") (pinfunction "I0_1") (pintype "input"))
      (node (ref "U6") (pin "5") (pinfunction "Q_5") (pintype "output"))
    )
    (net (code "102") (name "Net-(U3A-I2)") (class "Default")
      (node (ref "JP3") (pin "2") (pinfunction "2_2") (pintype "passive"))
      (node (ref "R4") (pin "1") (pinfunction "1_1") (pintype "passive"))
      (node (ref "U3") (pin "13") (pinfunction "I2_13") (pintype "input"))
    )
    (net (code "103") (name "Net-(U3B-I1)") (class "Default")
      (node (ref "U3") (pin "4") (pinfunction "I1_4") (pintype "input"))
      (node (ref "U4") (pin "4") (pinfunction "O_4") (pintype "output"))
      (node (ref "U7") (pin "2") (pinfunction "I1_2") (pintype "input"))
    )
    (net (code "104") (name "Net-(U3B-I2)") (class "Default")
      (node (ref "U3") (pin "5") (pinfunction "I2_5") (pintype "input"))
      (node (ref "U4") (pin "10") (pinfunction "O_10") (pintype "output"))
    )
    (net (code "105") (name "Net-(U3B-O)") (class "Default")
      (node (ref "U3") (pin "6") (pinfunction "O_6") (pintype "output"))
      (node (ref "U4") (pin "5") (pinfunction "I_5") (pintype "input"))
    )
    (net (code "106") (name "Net-(U3C-O)") (class "Default")
      (node (ref "U3") (pin "8") (pinfunction "O_8") (pintype "output"))
      (node (ref "U5") (pin "12") (pinfunction "D_12") (pintype "input"))
    )
    (net (code "107") (name "Net-(U4F-O)") (class "Default")
      (node (ref "U4") (pin "12") (pinfunction "O_12") (pintype "output"))
      (node (ref "U6") (pin "13") (pinfunction "CLR_13") (pintype "input"))
    )
    (net (code "108") (name "Net-(U5A-CLR)") (class "Default")
      (node (ref "U5") (pin "1") (pinfunction "CLR_1") (pintype "input"))
      (node (ref "U5") (pin "9") (pinfunction "Q_9") (pintype "output"))
    )
    (net (code "109") (name "Net-(U7C-O)") (class "Default")
      (node (ref "R5") (pin "1") (pinfunction "1_1") (pintype "passive"))
      (node (ref "U7") (pin "8") (pinfunction "O_8") (pintype "output"))
    )
    (net (code "110") (name "Net-(U10A-A)") (class "Default")
      (node (ref "U10") (pin "8") (pinfunction "A_8") (pintype "input"))
      (node (ref "U11") (pin "9") (pinfunction "Q4_9") (pintype "output"))
      (node (ref "U17") (pin "6") (pinfunction "A3_6") (pintype "input"))
    )
    (net (code "111") (name "Net-(U10A-B)") (class "Default")
      (node (ref "U10") (pin "9") (pinfunction "B_9") (pintype "input"))
      (node (ref "U11") (pin "12") (pinfunction "Q5_12") (pintype "output"))
      (node (ref "U17") (pin "15") (pinfunction "A3_15") (pintype "input"))
    )
    (net (code "112") (name "Net-(U10A-C)") (class "Default")
      (node (ref "U10") (pin "10") (pinfunction "C_10") (pintype "input"))
      (node (ref "U11") (pin "15") (pinfunction "Q6_15") (pintype "output"))
      (node (ref "U17") (pin "4") (pinfunction "A2_4") (pintype "input"))
    )
    (net (code "113") (name "Net-(U10A-D)") (class "Default")
      (node (ref "U10") (pin "11") (pinfunction "D_11") (pintype "input"))
      (node (ref "U11") (pin "6") (pinfunction "Q3_6") (pintype "output"))
      (node (ref "U17") (pin "13") (pinfunction "A2_13") (pintype "input"))
    )
    (net (code "114") (name "Net-(U10A-E)") (class "Default")
      (node (ref "U10") (pin "12") (pinfunction "E_12") (pintype "input"))
      (node (ref "U11") (pin "5") (pinfunction "Q2_5") (pintype "output"))
      (node (ref "U17") (pin "8") (pinfunction "A4_8") (pintype "input"))
    )
    (net (code "115") (name "Net-(U10A-F)") (class "Default")
      (node (ref "U10") (pin "13") (pinfunction "F_13") (pintype "input"))
      (node (ref "U11") (pin "19") (pinfunction "Q8_19") (pintype "output"))
      (node (ref "U17") (pin "2") (pinfunction "A1_2") (pintype "input"))
    )
    (net (code "116") (name "Net-(U10A-H)") (class "Default")
      (node (ref "U10") (pin "2") (pinfunction "H_2") (pintype "input"))
      (node (ref "U11") (pin "2") (pinfunction "Q1_2") (pintype "output"))
      (node (ref "U17") (pin "11") (pinfunction "A1_11") (pintype "input"))
    )
    (net (code "117") (name "Net-(U10A-I)") (class "Default")
      (node (ref "U10") (pin "4") (pinfunction "I_4") (pintype "input"))
      (node (ref "U11") (pin "16") (pinfunction "Q7_16") (pintype "output"))
      (node (ref "U17") (pin "17") (pinfunction "A4_17") (pintype "input"))
    )
    (net (code "118") (name "Net-(U10A-SOD)") (class "Default")
      (node (ref "U10") (pin "6") (pinfunction "SOD_6") (pintype "output"))
      (node (ref "U2") (pin "2") (pinfunction "I1_2") (pintype "input"))
    )
    (net (code "119") (name "Net-(U11A-CLK)") (class "Default")
      (node (ref "U11") (pin "11") (pinfunction "CLK_11") (pintype "input"))
      (node (ref "U4") (pin "6") (pinfunction "O_6") (pintype "output"))
      (node (ref "U4") (pin "9") (pinfunction "I_9") (pintype "input"))
      (node (ref "U6") (pin "3") (pinfunction "CLK_3") (pintype "input"))
    )
    (net (code "120") (name "Net-(U11A-D1)") (class "Default")
      (node (ref "U11") (pin "3") (pinfunction "D1_3") (pintype "input"))
      (node (ref "U12") (pin "4") (pinfunction "QB_4") (pintype "output"))
    )
    (net (code "121") (name "Net-(U11A-D2)") (class "Default")
      (node (ref "U11") (pin "4") (pinfunction "D2_4") (pintype "input"))
      (node (ref "U12") (pin "5") (pinfunction "QC_5") (pintype "output"))
    )
    (net (code "122") (name "Net-(U11A-D3)") (class "Default")
      (node (ref "U11") (pin "7") (pinfunction "D3_7") (pintype "input"))
      (node (ref "U12") (pin "6") (pinfunction "QD_6") (pintype "output"))
    )
    (net (code "123") (name "Net-(U11A-D4)") (class "Default")
      (node (ref "U11") (pin "8") (pinfunction "D4_8") (pintype "input"))
      (node (ref "U12") (pin "10") (pinfunction "QE_10") (pintype "output"))
    )
    (net (code "124") (name "Net-(U11A-D5)") (class "Default")
      (node (ref "U11") (pin "13") (pinfunction "D5_13") (pintype "input"))
      (node (ref "U12") (pin "11") (pinfunction "QF_11") (pintype "output"))
    )
    (net (code "125") (name "Net-(U11A-D6)") (class "Default")
      (node (ref "U11") (pin "14") (pinfunction "D6_14") (pintype "input"))
      (node (ref "U12") (pin "12") (pinfunction "QG_12") (pintype "output"))
    )
    (net (code "126") (name "Net-(U11A-D7)") (class "Default")
      (node (ref "U11") (pin "17") (pinfunction "D7_17") (pintype "input"))
      (node (ref "U12") (pin "13") (pinfunction "QH_13") (pintype "output"))
      (node (ref "U13") (pin "1") (pinfunction "A_1") (pintype "input"))
    )
    (net (code "127") (name "Net-(U11A-D8)") (class "Default")
      (node (ref "U11") (pin "18") (pinfunction "D8_18") (pintype "input"))
      (node (ref "U13") (pin "3") (pinfunction "QA_3") (pintype "output"))
    )
    (net (code "128") (name "Net-(U12A-CLR)") (class "Default")
      (node (ref "U12") (pin "9") (pinfunction "CLR_9") (pintype "input"))
      (node (ref "U13") (pin "9") (pinfunction "CLR_9") (pintype "input"))
      (node (ref "U7") (pin "3") (pinfunction "O_3") (pintype "output"))
    )
    (net (code "129") (name "Net-(U12A-QA)") (class "Default")
      (node (ref "U12") (pin "3") (pinfunction "QA_3") (pintype "output"))
      (node (ref "U6") (pin "2") (pinfunction "D_2") (pintype "input"))
    )
    (net (code "130") (name "Net-(U13A-QB)") (class "Default")
      (node (ref "U13") (pin "4") (pinfunction "QB_4") (pintype "output"))
      (node (ref "U3") (pin "3") (pinfunction "I0_3") (pintype "input"))
    )
    (net (code "131") (name "Net-(U13A-QC)") (class "Default")
      (node (ref "U13") (pin "5") (pinfunction "QC_5") (pintype "output"))
      (node (ref "U4") (pin "3") (pinfunction "I_3") (pintype "input"))
    )
    (net (code "132") (name "Net-(U14A-~{Q})") (class "Default")
      (node (ref "U14") (pin "6") (pinfunction "~{Q}_6") (pintype "output"))
      (node (ref "U7") (pin "5") (pinfunction "I1_5") (pintype "input"))
    )
    (net (code "133") (name "Net-(U14B-CLK)") (class "Default")
      (node (ref "U14") (pin "11") (pinfunction "CLK_11") (pintype "input"))
      (node (ref "U4") (pin "8") (pinfunction "O_8") (pintype "output"))
    )
    (net (code "134") (name "Net-(U14B-CLR)") (class "Default")
      (node (ref "U14") (pin "13") (pinfunction "CLR_13") (pintype "input"))
      (node (ref "U7") (pin "6") (pinfunction "O_6") (pintype "output"))
    )
    (net (code "135") (name "Net-(U15A-G)") (class "Default")
      (node (ref "U15") (pin "1") (pinfunction "G_1") (pintype "input"))
      (node (ref "U15") (pin "19") (pinfunction "G_19") (pintype "input"))
      (node (ref "U9") (pin "7") (pinfunction "Y7_7") (pintype "output"))
    )
    (net (code "136") (name "Net-(U16A-G)") (class "Default")
      (node (ref "U16") (pin "1") (pinfunction "G_1") (pintype "input"))
      (node (ref "U16") (pin "19") (pinfunction "G_19") (pintype "input"))
      (node (ref "U9") (pin "14") (pinfunction "Y1_14") (pintype "output"))
    )
    (net (code "137") (name "Net-(U18A-SEV)") (class "Default")
      (node (ref "U18") (pin "5") (pinfunction "SEV_5") (pintype "output"))
      (node (ref "U20") (pin "4") (pinfunction "F_4") (pintype "input"))
    )
    (net (code "138") (name "Net-(U19A-QH)") (class "Default")
      (node (ref "U19") (pin "9") (pinfunction "QH_9") (pintype "output"))
      (node (ref "U3") (pin "11") (pinfunction "I2_11") (pintype "input"))
    )
    (net (code "139") (name "Net-(U19A-SER)") (class "Default")
      (node (ref "U19") (pin "10") (pinfunction "SER_10") (pintype "input"))
      (node (ref "U20") (pin "9") (pinfunction "QH_9") (pintype "output"))
    )
    (net (code "140") (name "Net-(U19A-~{QH})") (class "Default")
      (node (ref "U19") (pin "7") (pinfunction "~{QH}_7") (pintype "output"))
      (node (ref "U7") (pin "9") (pinfunction "I0_9") (pintype "input"))
    )
    (net (code "141") (name "Net-(U22A-O)") (class "Default")
      (node (ref "U22") (pin "2") (pinfunction "O_2") (pintype "output"))
      (node (ref "U24") (pin "14") (pinfunction "CS0_14") (pintype "input"))
    )
    (net (code "142") (name "Net-(U22B-O)") (class "Default")
      (node (ref "U22") (pin "4") (pinfunction "O_4") (pintype "output"))
      (node (ref "U24") (pin "15") (pinfunction "CS1_15") (pintype "input"))
      (node (ref "U25") (pin "15") (pinfunction "CS1_15") (pintype "input"))
    )
    (net (code "143") (name "Net-(U22C-O)") (class "Default")
      (node (ref "U22") (pin "6") (pinfunction "O_6") (pintype "output"))
      (node (ref "U24") (pin "39") (pinfunction "RESET_39") (pintype "input"))
      (node (ref "U25") (pin "39") (pinfunction "RESET_39") (pintype "input"))
    )
    (net (code "144") (name "Net-(U22D-I)") (class "Default")
      (node (ref "JP1") (pin "2") (pinfunction "2_2") (pintype "passive"))
      (node (ref "R8") (pin "2") (pinfunction "2_2") (pintype "passive"))
      (node (ref "U22") (pin "9") (pinfunction "I_9") (pintype "input"))
    )
    (net (code "145") (name "Net-(U22D-O)") (class "Default")
      (node (ref "U22") (pin "8") (pinfunction "O_8") (pintype "output"))
      (node (ref "U3") (pin "1") (pinfunction "I0_1") (pintype "input"))
    )
    (net (code "146") (name "Net-(U22E-I)") (class "Default")
      (node (ref "JP2") (pin "2") (pinfunction "2_2") (pintype "passive"))
      (node (ref "R9") (pin "2") (pinfunction "2_2") (pintype "passive"))
      (node (ref "U22") (pin "11") (pinfunction "I_11") (pintype "input"))
    )
    (net (code "147") (name "Net-(U22E-O)") (class "Default")
      (node (ref "U22") (pin "10") (pinfunction "O_10") (pintype "output"))
      (node (ref "U3") (pin "2") (pinfunction "I1_2") (pintype "input"))
    )
    (net (code "148") (name "Net-(U22F-I)") (class "Default")
      (node (ref "U22") (pin "13") (pinfunction "I_13") (pintype "input"))
      (node (ref "U3") (pin "12") (pinfunction "O_12") (pintype "output"))
    )
    (net (code "149") (name "Net-(U24A-RCLK)") (class "Default")
      (node (ref "U24") (pin "10") (pinfunction "RCLK_10") (pintype "input"))
      (node (ref "U24") (pin "17") (pinfunction "~{BAUDOUT}_17") (pintype "output"))
    )
    (net (code "150") (name "Net-(U24A-RX)") (class "Default")
      (node (ref "U24") (pin "11") (pinfunction "RX_11") (pintype "input"))
      (node (ref "U26") (pin "17") (pinfunction "RY3_17") (pintype "output"))
    )
    (net (code "151") (name "Net-(U24A-TX)") (class "Default")
      (node (ref "U24") (pin "13") (pinfunction "TX_13") (pintype "output"))
      (node (ref "U26") (pin "15") (pinfunction "DA2_15") (pintype "input"))
    )
    (net (code "152") (name "Net-(U24A-XTAL1)") (class "Default")
      (node (ref "U24") (pin "18") (pinfunction "XTAL1_18") (pintype "input"))
      (node (ref "U25") (pin "18") (pinfunction "XTAL1_18") (pintype "input"))
      (node (ref "Y1") (pin "5") (pinfunction "FO_5") (pintype "output"))
    )
    (net (code "153") (name "Net-(U24A-~{CD})") (class "Default")
      (node (ref "U24") (pin "42") (pinfunction "~{CD}_42") (pintype "input"))
      (node (ref "U26") (pin "19") (pinfunction "RY1_19") (pintype "output"))
    )
    (net (code "154") (name "Net-(U24A-~{CTS})") (class "Default")
      (node (ref "U24") (pin "40") (pinfunction "~{CTS}_40") (pintype "input"))
      (node (ref "U26") (pin "14") (pinfunction "RY4_14") (pintype "output"))
    )
    (net (code "155") (name "Net-(U24A-~{DSR})") (class "Default")
      (node (ref "U24") (pin "41") (pinfunction "~{DSR}_41") (pintype "input"))
      (node (ref "U26") (pin "18") (pinfunction "RY2_18") (pintype "output"))
    )
    (net (code "156") (name "Net-(U24A-~{DTR})") (class "Default")
      (node (ref "U24") (pin "37") (pinfunction "~{DTR}_37") (pintype "output"))
      (node (ref "U26") (pin "13") (pinfunction "DA3_13") (pintype "input"))
    )
    (net (code "157") (name "Net-(U24A-~{OP1})") (class "Default")
      (node (ref "J4") (pin "1") (pinfunction "1_1") (pintype "passive"))
      (node (ref "U24") (pin "38") (pinfunction "~{OP1}_38") (pintype "output"))
    )
    (net (code "158") (name "Net-(U24A-~{OP2})") (class "Default")
      (node (ref "J4") (pin "2") (pinfunction "2_2") (pintype "passive"))
      (node (ref "U24") (pin "35") (pinfunction "~{OP2}_35") (pintype "output"))
    )
    (net (code "159") (name "Net-(U24A-~{RI})") (class "Default")
      (node (ref "U24") (pin "43") (pinfunction "~{RI}_43") (pintype "input"))
      (node (ref "U26") (pin "12") (pinfunction "RY5_12") (pintype "output"))
    )
    (net (code "160") (name "Net-(U24A-~{RTS})") (class "Default")
      (node (ref "U24") (pin "36") (pinfunction "~{RTS}_36") (pintype "output"))
      (node (ref "U26") (pin "16") (pinfunction "DA1_16") (pintype "input"))
    )
    (net (code "161") (name "Net-(U25A-RCLK)") (class "Default")
      (node (ref "U25") (pin "10") (pinfunction "RCLK_10") (pintype "input"))
      (node (ref "U25") (pin "17") (pinfunction "~{BAUDOUT}_17") (pintype "output"))
    )
    (net (code "162") (name "Net-(U25A-RX)") (class "Default")
      (node (ref "U25") (pin "11") (pinfunction "RX_11") (pintype "input"))
      (node (ref "U27") (pin "17") (pinfunction "RY3_17") (pintype "output"))
    )
    (net (code "163") (name "Net-(U25A-TX)") (class "Default")
      (node (ref "U25") (pin "13") (pinfunction "TX_13") (pintype "output"))
      (node (ref "U27") (pin "15") (pinfunction "DA2_15") (pintype "input"))
    )
    (net (code "164") (name "Net-(U25A-~{CD})") (class "Default")
      (node (ref "U25") (pin "42") (pinfunction "~{CD}_42") (pintype "input"))
      (node (ref "U27") (pin "19") (pinfunction "RY1_19") (pintype "output"))
    )
    (net (code "165") (name "Net-(U25A-~{CTS})") (class "Default")
      (node (ref "U25") (pin "40") (pinfunction "~{CTS}_40") (pintype "input"))
      (node (ref "U27") (pin "14") (pinfunction "RY4_14") (pintype "output"))
    )
    (net (code "166") (name "Net-(U25A-~{DSR})") (class "Default")
      (node (ref "U25") (pin "41") (pinfunction "~{DSR}_41") (pintype "input"))
      (node (ref "U27") (pin "18") (pinfunction "RY2_18") (pintype "output"))
    )
    (net (code "167") (name "Net-(U25A-~{DTR})") (class "Default")
      (node (ref "U25") (pin "37") (pinfunction "~{DTR}_37") (pintype "output"))
      (node (ref "U27") (pin "13") (pinfunction "DA3_13") (pintype "input"))
    )
    (net (code "168") (name "Net-(U25A-~{OP1})") (class "Default")
      (node (ref "J5") (pin "1") (pinfunction "1_1") (pintype "passive"))
      (node (ref "U25") (pin "38") (pinfunction "~{OP1}_38") (pintype "output"))
    )
    (net (code "169") (name "Net-(U25A-~{OP2})") (class "Default")
      (node (ref "J5") (pin "2") (pinfunction "2_2") (pintype "passive"))
      (node (ref "U25") (pin "35") (pinfunction "~{OP2}_35") (pintype "output"))
    )
    (net (code "170") (name "Net-(U25A-~{RI})") (class "Default")
      (node (ref "U25") (pin "43") (pinfunction "~{RI}_43") (pintype "input"))
      (node (ref "U27") (pin "12") (pinfunction "RY5_12") (pintype "output"))
    )
    (net (code "171") (name "Net-(U25A-~{RTS})") (class "Default")
      (node (ref "U25") (pin "36") (pinfunction "~{RTS}_36") (pintype "output"))
      (node (ref "U27") (pin "16") (pinfunction "DA1_16") (pintype "input"))
    )
    (net (code "172") (name "Net-(U26-DY1)") (class "Default")
      (node (ref "J1") (pin "P$7") (pinfunction "P$7_P$7") (pintype "bidirectional"))
      (node (ref "U26") (pin "5") (pinfunction "DY1_5") (pintype "output"))
    )
    (net (code "173") (name "Net-(U26-DY2)") (class "Default")
      (node (ref "J1") (pin "P$3") (pinfunction "P$3_P$3") (pintype "bidirectional"))
      (node (ref "U26") (pin "6") (pinfunction "DY2_6") (pintype "output"))
    )
    (net (code "174") (name "Net-(U26-DY3)") (class "Default")
      (node (ref "J1") (pin "P$4") (pinfunction "P$4_P$4") (pintype "bidirectional"))
      (node (ref "U26") (pin "8") (pinfunction "DY3_8") (pintype "output"))
    )
    (net (code "175") (name "Net-(U26-RA1)") (class "Default")
      (node (ref "J1") (pin "P$1") (pinfunction "P$1_P$1") (pintype "bidirectional"))
      (node (ref "U26") (pin "2") (pinfunction "RA1_2") (pintype "input"))
    )
    (net (code "176") (name "Net-(U26-RA2)") (class "Default")
      (node (ref "J1") (pin "P$6") (pinfunction "P$6_P$6") (pintype "bidirectional"))
      (node (ref "U26") (pin "3") (pinfunction "RA2_3") (pintype "input"))
    )
    (net (code "177") (name "Net-(U26-RA3)") (class "Default")
      (node (ref "J1") (pin "P$2") (pinfunction "P$2_P$2") (pintype "bidirectional"))
      (node (ref "U26") (pin "4") (pinfunction "RA3_4") (pintype "input"))
    )
    (net (code "178") (name "Net-(U26-RA4)") (class "Default")
      (node (ref "J1") (pin "P$8") (pinfunction "P$8_P$8") (pintype "bidirectional"))
      (node (ref "U26") (pin "7") (pinfunction "RA4_7") (pintype "input"))
    )
    (net (code "179") (name "Net-(U26-RA5)") (class "Default")
      (node (ref "J1") (pin "P$9") (pinfunction "P$9_P$9") (pintype "bidirectional"))
      (node (ref "U26") (pin "9") (pinfunction "RA5_9") (pintype "input"))
    )
    (net (code "180") (name "Net-(U27-DY1)") (class "Default")
      (node (ref "J2") (pin "P$7") (pinfunction "P$7_P$7") (pintype "bidirectional"))
      (node (ref "U27") (pin "5") (pinfunction "DY1_5") (pintype "output"))
    )
    (net (code "181") (name "Net-(U27-DY2)") (class "Default")
      (node (ref "J2") (pin "P$3") (pinfunction "P$3_P$3") (pintype "bidirectional"))
      (node (ref "U27") (pin "6") (pinfunction "DY2_6") (pintype "output"))
    )
    (net (code "182") (name "Net-(U27-DY3)") (class "Default")
      (node (ref "J2") (pin "P$4") (pinfunction "P$4_P$4") (pintype "bidirectional"))
      (node (ref "U27") (pin "8") (pinfunction "DY3_8") (pintype "output"))
    )
    (net (code "183") (name "Net-(U27-RA1)") (class "Default")
      (node (ref "J2") (pin "P$1") (pinfunction "P$1_P$1") (pintype "bidirectional"))
      (node (ref "U27") (pin "2") (pinfunction "RA1_2") (pintype "input"))
    )
    (net (code "184") (name "Net-(U27-RA2)") (class "Default")
      (node (ref "J2") (pin "P$6") (pinfunction "P$6_P$6") (pintype "bidirectional"))
      (node (ref "U27") (pin "3") (pinfunction "RA2_3") (pintype "input"))
    )
    (net (code "185") (name "Net-(U27-RA3)") (class "Default")
      (node (ref "J2") (pin "P$2") (pinfunction "P$2_P$2") (pintype "bidirectional"))
      (node (ref "U27") (pin "4") (pinfunction "RA3_4") (pintype "input"))
    )
    (net (code "186") (name "Net-(U27-RA4)") (class "Default")
      (node (ref "J2") (pin "P$8") (pinfunction "P$8_P$8") (pintype "bidirectional"))
      (node (ref "U27") (pin "7") (pinfunction "RA4_7") (pintype "input"))
    )
    (net (code "187") (name "Net-(U27-RA5)") (class "Default")
      (node (ref "J2") (pin "P$9") (pinfunction "P$9_P$9") (pintype "bidirectional"))
      (node (ref "U27") (pin "9") (pinfunction "RA5_9") (pintype "input"))
    )
    (net (code "188") (name "SHIELD") (class "Default")
      (node (ref "J1") (pin "S1") (pinfunction "P$10_S1") (pintype "bidirectional"))
      (node (ref "J1") (pin "S2") (pinfunction "P$10_S2") (pintype "bidirectional"))
      (node (ref "J2") (pin "S1") (pinfunction "P$10_S1") (pintype "bidirectional"))
      (node (ref "J2") (pin "S2") (pinfunction "P$10_S2") (pintype "bidirectional"))
      (node (ref "J3") (pin "G$1") (pinfunction "SHIELD_G$1") (pintype "bidirectional"))
      (node (ref "J3") (pin "G$2") (pinfunction "SHIELD_G$2") (pintype "bidirectional"))
      (node (ref "J3") (pin "G$3") (pinfunction "SHIELD_G$3") (pintype "bidirectional"))
      (node (ref "JP4") (pin "2") (pinfunction "2_2") (pintype "passive"))
      (node (ref "JP5") (pin "2") (pinfunction "2_2") (pintype "passive"))
      (node (ref "JP6") (pin "2") (pinfunction "2_2") (pintype "passive"))
      (node (ref "JP7") (pin "2") (pinfunction "2_2") (pintype "passive"))
    )
    (net (code "189") (name "VCC") (class "Default")
      (node (ref "C1") (pin "P$1") (pinfunction "1_P$1") (pintype "passive"))
      (node (ref "C10") (pin "P$1") (pinfunction "1_P$1") (pintype "passive"))
      (node (ref "C11") (pin "P$1") (pinfunction "1_P$1") (pintype "passive"))
      (node (ref "C12") (pin "P$1") (pinfunction "1_P$1") (pintype "passive"))
      (node (ref "C13") (pin "P$1") (pinfunction "1_P$1") (pintype "passive"))
      (node (ref "C14") (pin "P$1") (pinfunction "1_P$1") (pintype "passive"))
      (node (ref "C15") (pin "P$1") (pinfunction "1_P$1") (pintype "passive"))
      (node (ref "C16") (pin "P$1") (pinfunction "1_P$1") (pintype "passive"))
      (node (ref "C17") (pin "P$1") (pinfunction "1_P$1") (pintype "passive"))
      (node (ref "C18") (pin "P$1") (pinfunction "1_P$1") (pintype "passive"))
      (node (ref "C19") (pin "P$1") (pinfunction "1_P$1") (pintype "passive"))
      (node (ref "C2") (pin "P$1") (pinfunction "1_P$1") (pintype "passive"))
      (node (ref "C20") (pin "P$1") (pinfunction "1_P$1") (pintype "passive"))
      (node (ref "C21") (pin "P$1") (pinfunction "1_P$1") (pintype "passive"))
      (node (ref "C22") (pin "P$1") (pinfunction "1_P$1") (pintype "passive"))
      (node (ref "C23") (pin "P$1") (pinfunction "1_P$1") (pintype "passive"))
      (node (ref "C24") (pin "P$1") (pinfunction "1_P$1") (pintype "passive"))
      (node (ref "C25") (pin "P$1") (pinfunction "1_P$1") (pintype "passive"))
      (node (ref "C26") (pin "P$1") (pinfunction "1_P$1") (pintype "passive"))
      (node (ref "C27") (pin "P$1") (pinfunction "1_P$1") (pintype "passive"))
      (node (ref "C3") (pin "P$1") (pinfunction "1_P$1") (pintype "passive"))
      (node (ref "C30") (pin "+") (pinfunction "+_+") (pintype "passive"))
      (node (ref "C31") (pin "P$1") (pinfunction "1_P$1") (pintype "passive"))
      (node (ref "C33") (pin "P$1") (pinfunction "1_P$1") (pintype "passive"))
      (node (ref "C4") (pin "P$1") (pinfunction "1_P$1") (pintype "passive"))
      (node (ref "C5") (pin "P$1") (pinfunction "1_P$1") (pintype "passive"))
      (node (ref "C6") (pin "P$1") (pinfunction "1_P$1") (pintype "passive"))
      (node (ref "C7") (pin "P$1") (pinfunction "1_P$1") (pintype "passive"))
      (node (ref "C8") (pin "P$1") (pinfunction "1_P$1") (pintype "passive"))
      (node (ref "C9") (pin "P$1") (pinfunction "1_P$1") (pintype "passive"))
      (node (ref "CE0") (pin "5") (pinfunction "+5V_5") (pintype "bidirectional"))
      (node (ref "CE0") (pin "6") (pinfunction "+5V_6") (pintype "bidirectional"))
      (node (ref "J3") (pin "4") (pinfunction "4_4") (pintype "bidirectional"))
      (node (ref "R1") (pin "2") (pinfunction "2_2") (pintype "passive"))
      (node (ref "R4") (pin "2") (pinfunction "2_2") (pintype "passive"))
      (node (ref "R6") (pin "2") (pinfunction "2_2") (pintype "passive"))
      (node (ref "R7") (pin "1") (pinfunction "1_1") (pintype "passive"))
      (node (ref "RN1") (pin "1") (pinfunction "1_1") (pintype "passive"))
      (node (ref "U1") (pin "4") (pinfunction "/RES_4") (pintype "input"))
      (node (ref "U1") (pin "8") (pinfunction "VCC+_8") (pintype "power_in"))
      (node (ref "U14") (pin "10") (pinfunction "PRE_10") (pintype "input"))
      (node (ref "U14") (pin "12") (pinfunction "D_12") (pintype "input"))
      (node (ref "U14") (pin "2") (pinfunction "D_2") (pintype "input"))
      (node (ref "U14") (pin "4") (pinfunction "PRE_4") (pintype "input"))
      (node (ref "U2") (pin "4") (pinfunction "I0_4") (pintype "input"))
      (node (ref "U2") (pin "5") (pinfunction "I1_5") (pintype "input"))
      (node (ref "U20") (pin "10") (pinfunction "SER_10") (pintype "input"))
      (node (ref "U20") (pin "11") (pinfunction "A_11") (pintype "input"))
      (node (ref "U20") (pin "12") (pinfunction "B_12") (pintype "input"))
      (node (ref "U20") (pin "13") (pinfunction "C_13") (pintype "input"))
      (node (ref "U20") (pin "14") (pinfunction "D_14") (pintype "input"))
      (node (ref "U20") (pin "3") (pinfunction "E_3") (pintype "input"))
      (node (ref "U26") (pin "20") (pinfunction "VCC_20") (pintype "power_in"))
      (node (ref "U27") (pin "20") (pinfunction "VCC_20") (pintype "power_in"))
      (node (ref "U5") (pin "2") (pinfunction "D_2") (pintype "input"))
      (node (ref "U5") (pin "4") (pinfunction "PRE_4") (pintype "input"))
      (node (ref "U6") (pin "10") (pinfunction "PRE_10") (pintype "input"))
      (node (ref "U6") (pin "12") (pinfunction "D_12") (pintype "input"))
      (node (ref "U6") (pin "4") (pinfunction "PRE_4") (pintype "input"))
      (node (ref "U7") (pin "12") (pinfunction "I0_12") (pintype "input"))
      (node (ref "U7") (pin "13") (pinfunction "I1_13") (pintype "input"))
      (node (ref "Y1") (pin "1") (pinfunction "OE_1") (pintype "input"))
      (node (ref "Y1") (pin "8") (pinfunction "VCC_8") (pintype "power_in"))
    )
    (net (code "190") (name "unconnected-(CE0-+3.3V-Pad2)") (class "Default")
      (node (ref "CE0") (pin "2") (pinfunction "+3.3V_2") (pintype "bidirectional"))
    )
    (net (code "191") (name "unconnected-(CE0-+5VSB-Pad8)") (class "Default")
      (node (ref "CE0") (pin "8") (pinfunction "+5VSB_8") (pintype "bidirectional"))
    )
    (net (code "192") (name "unconnected-(CE0-A5-Pad28)") (class "Default")
      (node (ref "CE0") (pin "28") (pinfunction "A5_28") (pintype "bidirectional"))
    )
    (net (code "193") (name "unconnected-(CE0-A6-Pad29)") (class "Default")
      (node (ref "CE0") (pin "29") (pinfunction "A6_29") (pintype "bidirectional"))
    )
    (net (code "194") (name "unconnected-(CE0-A7-Pad30)") (class "Default")
      (node (ref "CE0") (pin "30") (pinfunction "A7_30") (pintype "bidirectional"))
    )
    (net (code "195") (name "unconnected-(CE0-A8-Pad31)") (class "Default")
      (node (ref "CE0") (pin "31") (pinfunction "A8_31") (pintype "bidirectional"))
    )
    (net (code "196") (name "unconnected-(CE0-A9-Pad32)") (class "Default")
      (node (ref "CE0") (pin "32") (pinfunction "A9_32") (pintype "bidirectional"))
    )
    (net (code "197") (name "unconnected-(CE0-A10-Pad33)") (class "Default")
      (node (ref "CE0") (pin "33") (pinfunction "A10_33") (pintype "bidirectional"))
    )
    (net (code "198") (name "unconnected-(CE0-A11-Pad34)") (class "Default")
      (node (ref "CE0") (pin "34") (pinfunction "A11_34") (pintype "bidirectional"))
    )
    (net (code "199") (name "unconnected-(CE0-A12-Pad35)") (class "Default")
      (node (ref "CE0") (pin "35") (pinfunction "A12_35") (pintype "bidirectional"))
    )
    (net (code "200") (name "unconnected-(CE0-A13-Pad36)") (class "Default")
      (node (ref "CE0") (pin "36") (pinfunction "A13_36") (pintype "bidirectional"))
    )
    (net (code "201") (name "unconnected-(CE0-A14-Pad37)") (class "Default")
      (node (ref "CE0") (pin "37") (pinfunction "A14_37") (pintype "bidirectional"))
    )
    (net (code "202") (name "unconnected-(CE0-A15-Pad38)") (class "Default")
      (node (ref "CE0") (pin "38") (pinfunction "A15_38") (pintype "bidirectional"))
    )
    (net (code "203") (name "unconnected-(CE0-A16-Pad39)") (class "Default")
      (node (ref "CE0") (pin "39") (pinfunction "A16_39") (pintype "bidirectional"))
    )
    (net (code "204") (name "unconnected-(CE0-A17-Pad40)") (class "Default")
      (node (ref "CE0") (pin "40") (pinfunction "A17_40") (pintype "bidirectional"))
    )
    (net (code "205") (name "unconnected-(CE0-A18-Pad41)") (class "Default")
      (node (ref "CE0") (pin "41") (pinfunction "A18_41") (pintype "bidirectional"))
    )
    (net (code "206") (name "unconnected-(CE0-A19-Pad42)") (class "Default")
      (node (ref "CE0") (pin "42") (pinfunction "A19_42") (pintype "bidirectional"))
    )
    (net (code "207") (name "unconnected-(CE0-CLK-Pad15)") (class "Default")
      (node (ref "CE0") (pin "15") (pinfunction "CLK_15") (pintype "bidirectional"))
    )
    (net (code "208") (name "unconnected-(CE0-~{BUSACK}-Pad20)") (class "Default")
      (node (ref "CE0") (pin "20") (pinfunction "~{BUSACK}_20") (pintype "bidirectional"))
    )
    (net (code "209") (name "unconnected-(CE0-~{BUSRQ}-Pad10)") (class "Default")
      (node (ref "CE0") (pin "10") (pinfunction "~{BUSRQ}_10") (pintype "bidirectional"))
    )
    (net (code "210") (name "unconnected-(CE0-~{CBR}-Pad12)") (class "Default")
      (node (ref "CE0") (pin "12") (pinfunction "~{CBR}_12") (pintype "bidirectional"))
    )
    (net (code "211") (name "unconnected-(CE0-~{CINH}-Pad13)") (class "Default")
      (node (ref "CE0") (pin "13") (pinfunction "~{CINH}_13") (pintype "bidirectional"))
    )
    (net (code "212") (name "unconnected-(CE0-~{FETCH}-Pad19)") (class "Default")
      (node (ref "CE0") (pin "19") (pinfunction "~{FETCH}_19") (pintype "bidirectional"))
    )
    (net (code "213") (name "unconnected-(CE0-~{HALT}-Pad17)") (class "Default")
      (node (ref "CE0") (pin "17") (pinfunction "~{HALT}_17") (pintype "bidirectional"))
    )
    (net (code "214") (name "unconnected-(CE0-~{INH}-Pad11)") (class "Default")
      (node (ref "CE0") (pin "11") (pinfunction "~{INH}_11") (pintype "bidirectional"))
    )
    (net (code "215") (name "unconnected-(CE0-~{INT}-Pad51)") (class "Default")
      (node (ref "CE0") (pin "51") (pinfunction "~{INT}_51") (pintype "bidirectional"))
    )
    (net (code "216") (name "unconnected-(CE0-~{IO}-Pad16)") (class "Default")
      (node (ref "CE0") (pin "16") (pinfunction "~{IO}_16") (pintype "bidirectional"))
    )
    (net (code "217") (name "unconnected-(CE0-~{IRQ0}-Pad53)") (class "Default")
      (node (ref "CE0") (pin "53") (pinfunction "~{IRQ0}_53") (pintype "bidirectional"))
    )
    (net (code "218") (name "unconnected-(CE0-~{IRQ1}-Pad54)") (class "Default")
      (node (ref "CE0") (pin "54") (pinfunction "~{IRQ1}_54") (pintype "bidirectional"))
    )
    (net (code "219") (name "unconnected-(CE0-~{IRQ2}-Pad55)") (class "Default")
      (node (ref "CE0") (pin "55") (pinfunction "~{IRQ2}_55") (pintype "bidirectional"))
    )
    (net (code "220") (name "unconnected-(CE0-~{IRQ3}-Pad56)") (class "Default")
      (node (ref "CE0") (pin "56") (pinfunction "~{IRQ3}_56") (pintype "bidirectional"))
    )
    (net (code "221") (name "unconnected-(CE0-~{IRQ4}-Pad57)") (class "Default")
      (node (ref "CE0") (pin "57") (pinfunction "~{IRQ4}_57") (pintype "bidirectional"))
    )
    (net (code "222") (name "unconnected-(CE0-~{IRQ5}-Pad58)") (class "Default")
      (node (ref "CE0") (pin "58") (pinfunction "~{IRQ5}_58") (pintype "bidirectional"))
    )
    (net (code "223") (name "unconnected-(CE0-~{IRQ6}-Pad59)") (class "Default")
      (node (ref "CE0") (pin "59") (pinfunction "~{IRQ6}_59") (pintype "bidirectional"))
    )
    (net (code "224") (name "unconnected-(CE0-~{IRQ7}-Pad60)") (class "Default")
      (node (ref "CE0") (pin "60") (pinfunction "~{IRQ7}_60") (pintype "bidirectional"))
    )
    (net (code "225") (name "unconnected-(CE0-~{NMI}-Pad61)") (class "Default")
      (node (ref "CE0") (pin "61") (pinfunction "~{NMI}_61") (pintype "bidirectional"))
    )
    (net (code "226") (name "unconnected-(CE0-~{WAIT}-Pad18)") (class "Default")
      (node (ref "CE0") (pin "18") (pinfunction "~{WAIT}_18") (pintype "bidirectional"))
    )
    (net (code "227") (name "unconnected-(J3-Pad2)") (class "Default")
      (node (ref "J3") (pin "2") (pinfunction "2_2") (pintype "bidirectional"))
    )
    (net (code "228") (name "unconnected-(J3-Pad6)") (class "Default")
      (node (ref "J3") (pin "6") (pinfunction "6_6") (pintype "bidirectional"))
    )
    (net (code "229") (name "unconnected-(U2B-O-Pad6)") (class "Default")
      (node (ref "U2") (pin "6") (pinfunction "O_6") (pintype "output"))
    )
    (net (code "230") (name "unconnected-(U5B-~{Q}-Pad8)") (class "Default")
      (node (ref "U5") (pin "8") (pinfunction "~{Q}_8") (pintype "output"))
    )
    (net (code "231") (name "unconnected-(U6A-~{Q}-Pad6)") (class "Default")
      (node (ref "U6") (pin "6") (pinfunction "~{Q}_6") (pintype "output"))
    )
    (net (code "232") (name "unconnected-(U6B-Q-Pad9)") (class "Default")
      (node (ref "U6") (pin "9") (pinfunction "Q_9") (pintype "output"))
    )
    (net (code "233") (name "unconnected-(U7D-O-Pad11)") (class "Default")
      (node (ref "U7") (pin "11") (pinfunction "O_11") (pintype "output"))
    )
    (net (code "234") (name "unconnected-(U8A-Y1-Pad14)") (class "Default")
      (node (ref "U8") (pin "14") (pinfunction "Y1_14") (pintype "output"))
    )
    (net (code "235") (name "unconnected-(U8A-Y2-Pad13)") (class "Default")
      (node (ref "U8") (pin "13") (pinfunction "Y2_13") (pintype "output"))
    )
    (net (code "236") (name "unconnected-(U8A-Y3-Pad12)") (class "Default")
      (node (ref "U8") (pin "12") (pinfunction "Y3_12") (pintype "output"))
    )
    (net (code "237") (name "unconnected-(U8A-Y4-Pad11)") (class "Default")
      (node (ref "U8") (pin "11") (pinfunction "Y4_11") (pintype "output"))
    )
    (net (code "238") (name "unconnected-(U8A-Y5-Pad10)") (class "Default")
      (node (ref "U8") (pin "10") (pinfunction "Y5_10") (pintype "output"))
    )
    (net (code "239") (name "unconnected-(U8A-Y6-Pad9)") (class "Default")
      (node (ref "U8") (pin "9") (pinfunction "Y6_9") (pintype "output"))
    )
    (net (code "240") (name "unconnected-(U8A-Y7-Pad7)") (class "Default")
      (node (ref "U8") (pin "7") (pinfunction "Y7_7") (pintype "output"))
    )
    (net (code "241") (name "unconnected-(U9A-Y2-Pad13)") (class "Default")
      (node (ref "U9") (pin "13") (pinfunction "Y2_13") (pintype "output"))
    )
    (net (code "242") (name "unconnected-(U9A-Y3-Pad12)") (class "Default")
      (node (ref "U9") (pin "12") (pinfunction "Y3_12") (pintype "output"))
    )
    (net (code "243") (name "unconnected-(U9A-Y4-Pad11)") (class "Default")
      (node (ref "U9") (pin "11") (pinfunction "Y4_11") (pintype "output"))
    )
    (net (code "244") (name "unconnected-(U9A-Y5-Pad10)") (class "Default")
      (node (ref "U9") (pin "10") (pinfunction "Y5_10") (pintype "output"))
    )
    (net (code "245") (name "unconnected-(U9A-Y6-Pad9)") (class "Default")
      (node (ref "U9") (pin "9") (pinfunction "Y6_9") (pintype "output"))
    )
    (net (code "246") (name "unconnected-(U10A-SEV-Pad5)") (class "Default")
      (node (ref "U10") (pin "5") (pinfunction "SEV_5") (pintype "output"))
    )
    (net (code "247") (name "unconnected-(U13A-QD-Pad6)") (class "Default")
      (node (ref "U13") (pin "6") (pinfunction "QD_6") (pintype "output"))
    )
    (net (code "248") (name "unconnected-(U13A-QE-Pad10)") (class "Default")
      (node (ref "U13") (pin "10") (pinfunction "QE_10") (pintype "output"))
    )
    (net (code "249") (name "unconnected-(U13A-QF-Pad11)") (class "Default")
      (node (ref "U13") (pin "11") (pinfunction "QF_11") (pintype "output"))
    )
    (net (code "250") (name "unconnected-(U13A-QG-Pad12)") (class "Default")
      (node (ref "U13") (pin "12") (pinfunction "QG_12") (pintype "output"))
    )
    (net (code "251") (name "unconnected-(U13A-QH-Pad13)") (class "Default")
      (node (ref "U13") (pin "13") (pinfunction "QH_13") (pintype "output"))
    )
    (net (code "252") (name "unconnected-(U14A-Q-Pad5)") (class "Default")
      (node (ref "U14") (pin "5") (pinfunction "Q_5") (pintype "output"))
    )
    (net (code "253") (name "unconnected-(U18A-SOD-Pad6)") (class "Default")
      (node (ref "U18") (pin "6") (pinfunction "SOD_6") (pintype "output"))
    )
    (net (code "254") (name "unconnected-(U20A-~{QH}-Pad7)") (class "Default")
      (node (ref "U20") (pin "7") (pinfunction "~{QH}_7") (pintype "output"))
    )
    (net (code "255") (name "unconnected-(U24A-XTAL2-Pad19)") (class "Default")
      (node (ref "U24") (pin "19") (pinfunction "XTAL2_19") (pintype "output"))
    )
    (net (code "256") (name "unconnected-(U24A-~{DDIS}-Pad26)") (class "Default")
      (node (ref "U24") (pin "26") (pinfunction "~{DDIS}_26") (pintype "output"))
    )
    (net (code "257") (name "unconnected-(U24A-~{RXRDY}-Pad32)") (class "Default")
      (node (ref "U24") (pin "32") (pinfunction "~{RXRDY}_32") (pintype "output"))
    )
    (net (code "258") (name "unconnected-(U24A-~{TXRDY}-Pad27)") (class "Default")
      (node (ref "U24") (pin "27") (pinfunction "~{TXRDY}_27") (pintype "output"))
    )
    (net (code "259") (name "unconnected-(U25A-XTAL2-Pad19)") (class "Default")
      (node (ref "U25") (pin "19") (pinfunction "XTAL2_19") (pintype "output"))
    )
    (net (code "260") (name "unconnected-(U25A-~{DDIS}-Pad26)") (class "Default")
      (node (ref "U25") (pin "26") (pinfunction "~{DDIS}_26") (pintype "output"))
    )
    (net (code "261") (name "unconnected-(U25A-~{RXRDY}-Pad32)") (class "Default")
      (node (ref "U25") (pin "32") (pinfunction "~{RXRDY}_32") (pintype "output"))
    )
    (net (code "262") (name "unconnected-(U25A-~{TXRDY}-Pad27)") (class "Default")
      (node (ref "U25") (pin "27") (pinfunction "~{TXRDY}_27") (pintype "output"))
    )
    (net (code "263") (name "~{BCSX}") (class "Default")
      (node (ref "CE0") (pin "9") (pinfunction "~{CSX}_9") (pintype "bidirectional"))
      (node (ref "U21") (pin "2") (pinfunction "A1_2") (pintype "input"))
    )
    (net (code "264") (name "~{BRD}") (class "Default")
      (node (ref "CE0") (pin "21") (pinfunction "~{RD}_21") (pintype "bidirectional"))
      (node (ref "U21") (pin "4") (pinfunction "A2_4") (pintype "input"))
    )
    (net (code "265") (name "~{BRST}") (class "Default")
      (node (ref "CE0") (pin "14") (pinfunction "~{RST}_14") (pintype "bidirectional"))
      (node (ref "U2") (pin "13") (pinfunction "I1_13") (pintype "input"))
    )
    (net (code "266") (name "~{BWR}") (class "Default")
      (node (ref "CE0") (pin "22") (pinfunction "~{WR}_22") (pintype "bidirectional"))
      (node (ref "U21") (pin "17") (pinfunction "A4_17") (pintype "input"))
    )
    (net (code "267") (name "~{CSX}") (class "Default")
      (node (ref "U21") (pin "18") (pinfunction "Y1_18") (pintype "tri_state"))
      (node (ref "U23") (pin "19") (pinfunction "G_19") (pintype "input"))
      (node (ref "U24") (pin "16") (pinfunction "~{CS2}_16") (pintype "input"))
      (node (ref "U25") (pin "16") (pinfunction "~{CS2}_16") (pintype "input"))
      (node (ref "U8") (pin "4") (pinfunction "G2A_4") (pintype "input"))
      (node (ref "U9") (pin "4") (pinfunction "G2A_4") (pintype "input"))
    )
    (net (code "268") (name "~{CS_KBR}") (class "Default")
      (node (ref "U14") (pin "3") (pinfunction "CLK_3") (pintype "input"))
      (node (ref "U17") (pin "1") (pinfunction "G_1") (pintype "input"))
      (node (ref "U17") (pin "19") (pinfunction "G_19") (pintype "input"))
      (node (ref "U9") (pin "15") (pinfunction "Y0_15") (pintype "output"))
    )
    (net (code "269") (name "~{CS_KBW}") (class "Default")
      (node (ref "U19") (pin "1") (pinfunction "SH/~{LD}_1") (pintype "input"))
      (node (ref "U20") (pin "1") (pinfunction "SH/~{LD}_1") (pintype "input"))
      (node (ref "U5") (pin "10") (pinfunction "PRE_10") (pintype "input"))
      (node (ref "U5") (pin "3") (pinfunction "CLK_3") (pintype "input"))
      (node (ref "U8") (pin "15") (pinfunction "Y0_15") (pintype "output"))
    )
    (net (code "270") (name "~{INT_KB}") (class "Default")
      (node (ref "JP3") (pin "1") (pinfunction "1_1") (pintype "passive"))
      (node (ref "U14") (pin "8") (pinfunction "~{Q}_8") (pintype "output"))
    )
    (net (code "271") (name "~{IRQX}") (class "Default")
      (node (ref "CE0") (pin "52") (pinfunction "~{IRQX}_52") (pintype "bidirectional"))
      (node (ref "U22") (pin "12") (pinfunction "O_12") (pintype "output"))
    )
    (net (code "272") (name "~{KB_DATA}") (class "Default")
      (node (ref "U12") (pin "1") (pinfunction "A_1") (pintype "input"))
      (node (ref "U3") (pin "9") (pinfunction "I0_9") (pintype "input"))
      (node (ref "U4") (pin "2") (pinfunction "O_2") (pintype "output"))
    )
    (net (code "273") (name "~{KB_WRCYCLE}") (class "Default")
      (node (ref "U12") (pin "2") (pinfunction "B_2") (pintype "input"))
      (node (ref "U13") (pin "2") (pinfunction "B_2") (pintype "input"))
      (node (ref "U19") (pin "15") (pinfunction "INH_15") (pintype "input"))
      (node (ref "U20") (pin "15") (pinfunction "INH_15") (pintype "input"))
      (node (ref "U5") (pin "6") (pinfunction "~{Q}_6") (pintype "output"))
    )
    (net (code "274") (name "~{RD}") (class "Default")
      (node (ref "U21") (pin "16") (pinfunction "Y2_16") (pintype "tri_state"))
      (node (ref "U23") (pin "1") (pinfunction "DIR_1") (pintype "input"))
      (node (ref "U24") (pin "24") (pinfunction "~{IOR}_24") (pintype "input"))
      (node (ref "U25") (pin "24") (pinfunction "~{IOR}_24") (pintype "input"))
      (node (ref "U9") (pin "5") (pinfunction "G2B_5") (pintype "input"))
    )
    (net (code "275") (name "~{RST}") (class "Default")
      (node (ref "U11") (pin "1") (pinfunction "CLR_1") (pintype "input"))
      (node (ref "U2") (pin "11") (pinfunction "O_11") (pintype "output"))
      (node (ref "U22") (pin "5") (pinfunction "I_5") (pintype "input"))
      (node (ref "U5") (pin "13") (pinfunction "CLR_13") (pintype "input"))
      (node (ref "U6") (pin "1") (pinfunction "CLR_1") (pintype "input"))
      (node (ref "U7") (pin "1") (pinfunction "I0_1") (pintype "input"))
      (node (ref "U7") (pin "4") (pinfunction "I0_4") (pintype "input"))
    )
    (net (code "276") (name "~{WR}") (class "Default")
      (node (ref "U21") (pin "3") (pinfunction "Y4_3") (pintype "tri_state"))
      (node (ref "U24") (pin "20") (pinfunction "~{IOW}_20") (pintype "input"))
      (node (ref "U25") (pin "20") (pinfunction "~{IOW}_20") (pintype "input"))
      (node (ref "U8") (pin "5") (pinfunction "G2B_5") (pintype "input"))
    )
  )
)
